# 1VFAT_OH1_OCT1.net
KiCad netlist of a schematic drawn in Altium Designer
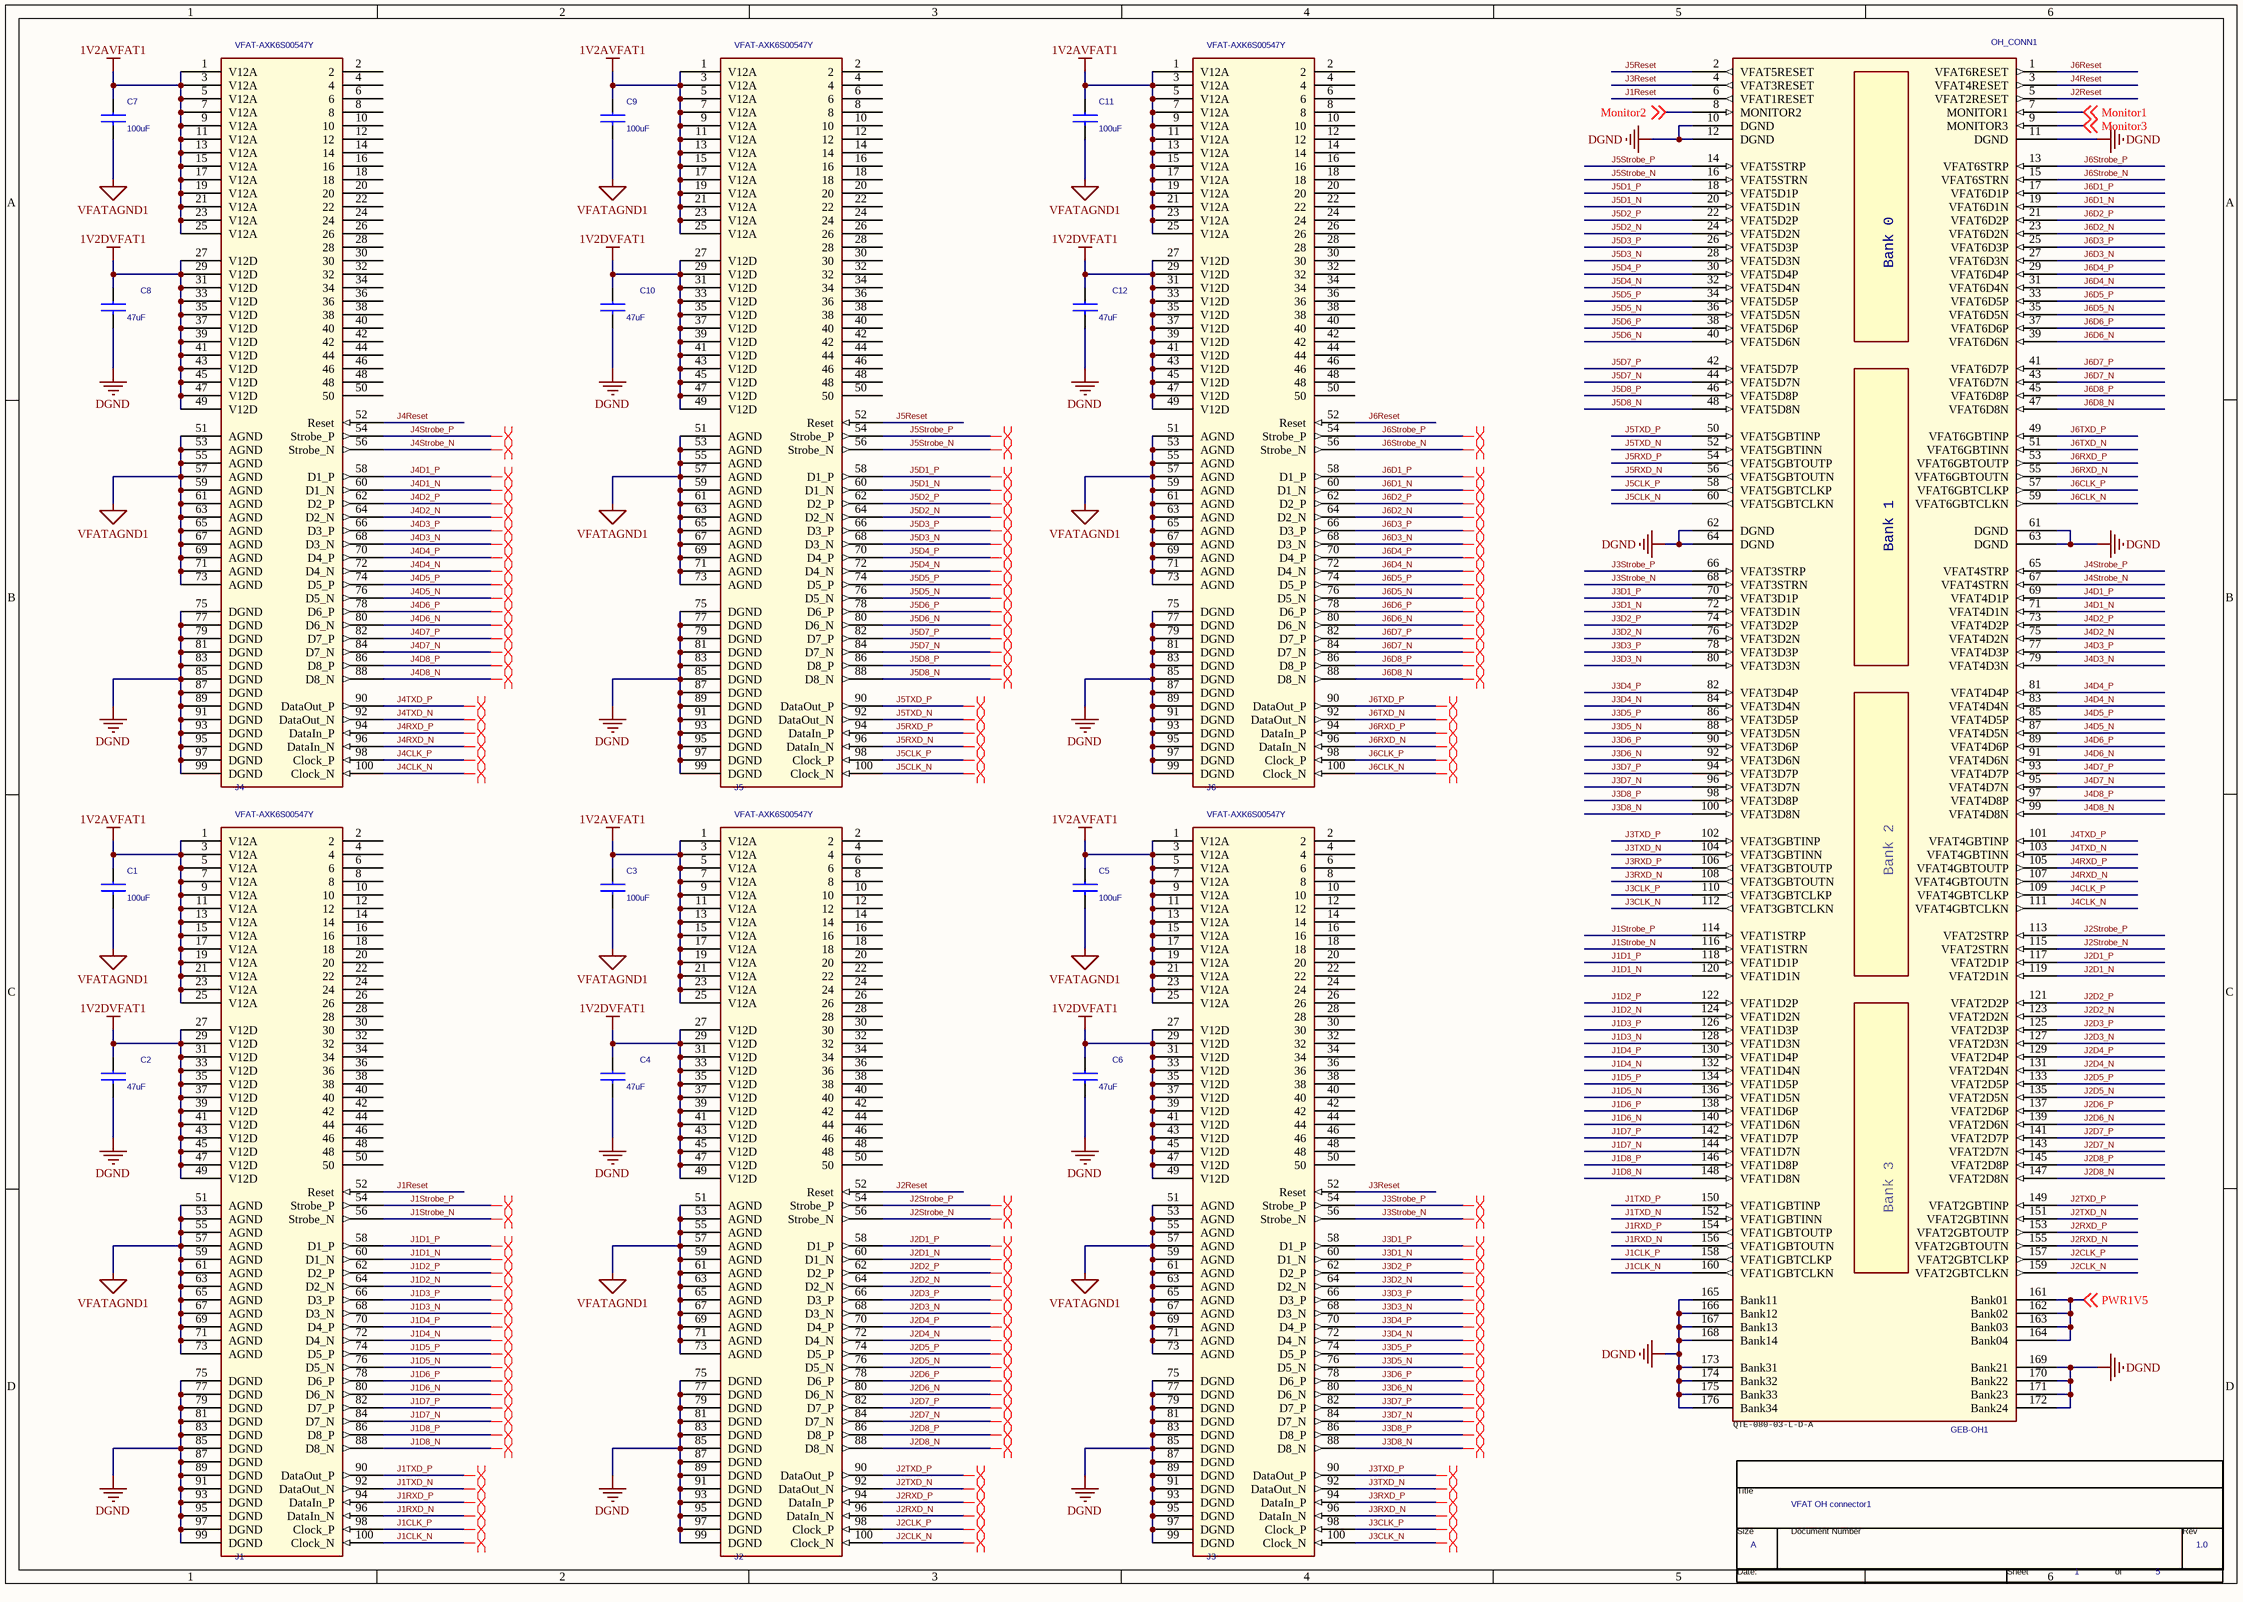
[diagram p0: 1VFAT_OH1_OCT1.SchDoc]

(export (version "E")
  (design (tool "Eeschema 10.0.6"))
  (components
    (comp (ref "*")
      (value "TitleBlock0")
      (fields
        (field (name "PAGE COUNT") "5")
        (field (name "PAGE NUMBER") "1")
        (field (name "PAGE SIZE") "A")
        (field (name "TITLE") "VFAT OH connector1")
        (field (name "REVCODE") "1.0")
      )
      (libsource (lib "*") (part "TitleBlock0"))
    )
    (comp (ref "C1") (value "100uF") (footprint "C1210") (libsource (lib "*") (part "CAP NP")))
    (comp (ref "C2") (value "47uF") (footprint "C1206") (libsource (lib "*") (part "CAP NP")))
    (comp (ref "C3") (value "100uF") (footprint "C1210") (libsource (lib "*") (part "CAP NP")))
    (comp (ref "C4") (value "47uF") (footprint "C1206") (libsource (lib "*") (part "CAP NP")))
    (comp (ref "C5") (value "100uF") (footprint "C1210") (libsource (lib "*") (part "CAP NP")))
    (comp (ref "C6") (value "47uF") (footprint "C1206") (libsource (lib "*") (part "CAP NP")))
    (comp (ref "C7") (value "100uF") (footprint "C1210") (libsource (lib "*") (part "CAP NP")))
    (comp (ref "C8") (value "47uF") (footprint "C1206") (libsource (lib "*") (part "CAP NP")))
    (comp (ref "C9") (value "100uF") (footprint "C1210") (libsource (lib "*") (part "CAP NP")))
    (comp (ref "C10") (value "47uF") (footprint "C1206") (libsource (lib "*") (part "CAP NP")))
    (comp (ref "C11") (value "100uF") (footprint "C1210") (libsource (lib "*") (part "CAP NP")))
    (comp (ref "C12") (value "47uF") (footprint "C1206") (libsource (lib "*") (part "CAP NP")))
    (comp (ref "J1")
      (value "VFAT-AXK6S00547Y")
      (footprint "panasonic100")
      (libsource (lib "*") (part "VFAT-AXK6S00547Y"))
    )
    (comp (ref "J2")
      (value "VFAT-AXK6S00547Y")
      (footprint "panasonic100")
      (libsource (lib "*") (part "VFAT-AXK6S00547Y"))
    )
    (comp (ref "J3")
      (value "VFAT-AXK6S00547Y")
      (footprint "panasonic100")
      (libsource (lib "*") (part "VFAT-AXK6S00547Y"))
    )
    (comp (ref "J4")
      (value "VFAT-AXK6S00547Y")
      (footprint "panasonic100")
      (libsource (lib "*") (part "VFAT-AXK6S00547Y"))
    )
    (comp (ref "J5")
      (value "VFAT-AXK6S00547Y")
      (footprint "panasonic100")
      (libsource (lib "*") (part "VFAT-AXK6S00547Y"))
    )
    (comp (ref "J6")
      (value "VFAT-AXK6S00547Y")
      (footprint "panasonic100")
      (libsource (lib "*") (part "VFAT-AXK6S00547Y"))
    )
    (comp (ref "OH_CONN1") (value "GEB-OH1") (footprint "samtec160") (libsource (lib "*") (part "GEB-OH1")))
  )
  (nets
    (net (code "1") (name "/J1CLK_N") (class "Default")
      (node (ref "J1") (pin "100") (pinfunction "Clock_N_100") (pintype "input"))
      (node (ref "OH_CONN1") (pin "160") (pinfunction "VFAT1GBTCLKN_160") (pintype "output"))
    )
    (net (code "2") (name "/J1CLK_P") (class "Default")
      (node (ref "J1") (pin "98") (pinfunction "Clock_P_98") (pintype "input"))
      (node (ref "OH_CONN1") (pin "158") (pinfunction "VFAT1GBTCLKP_158") (pintype "output"))
    )
    (net (code "3") (name "/J1D1_N") (class "Default")
      (node (ref "J1") (pin "60") (pinfunction "D1_N_60") (pintype "output"))
      (node (ref "OH_CONN1") (pin "120") (pinfunction "VFAT1D1N_120") (pintype "input"))
    )
    (net (code "4") (name "/J1D1_P") (class "Default")
      (node (ref "J1") (pin "58") (pinfunction "D1_P_58") (pintype "output"))
      (node (ref "OH_CONN1") (pin "118") (pinfunction "VFAT1D1P_118") (pintype "input"))
    )
    (net (code "5") (name "/J1D2_N") (class "Default")
      (node (ref "J1") (pin "64") (pinfunction "D2_N_64") (pintype "output"))
      (node (ref "OH_CONN1") (pin "124") (pinfunction "VFAT1D2N_124") (pintype "input"))
    )
    (net (code "6") (name "/J1D2_P") (class "Default")
      (node (ref "J1") (pin "62") (pinfunction "D2_P_62") (pintype "output"))
      (node (ref "OH_CONN1") (pin "122") (pinfunction "VFAT1D2P_122") (pintype "input"))
    )
    (net (code "7") (name "/J1D3_N") (class "Default")
      (node (ref "J1") (pin "68") (pinfunction "D3_N_68") (pintype "output"))
      (node (ref "OH_CONN1") (pin "128") (pinfunction "VFAT1D3N_128") (pintype "input"))
    )
    (net (code "8") (name "/J1D3_P") (class "Default")
      (node (ref "J1") (pin "66") (pinfunction "D3_P_66") (pintype "output"))
      (node (ref "OH_CONN1") (pin "126") (pinfunction "VFAT1D3P_126") (pintype "input"))
    )
    (net (code "9") (name "/J1D4_N") (class "Default")
      (node (ref "J1") (pin "72") (pinfunction "D4_N_72") (pintype "output"))
      (node (ref "OH_CONN1") (pin "132") (pinfunction "VFAT1D4N_132") (pintype "input"))
    )
    (net (code "10") (name "/J1D4_P") (class "Default")
      (node (ref "J1") (pin "70") (pinfunction "D4_P_70") (pintype "output"))
      (node (ref "OH_CONN1") (pin "130") (pinfunction "VFAT1D4P_130") (pintype "input"))
    )
    (net (code "11") (name "/J1D5_N") (class "Default")
      (node (ref "J1") (pin "76") (pinfunction "D5_N_76") (pintype "output"))
      (node (ref "OH_CONN1") (pin "136") (pinfunction "VFAT1D5N_136") (pintype "input"))
    )
    (net (code "12") (name "/J1D5_P") (class "Default")
      (node (ref "J1") (pin "74") (pinfunction "D5_P_74") (pintype "output"))
      (node (ref "OH_CONN1") (pin "134") (pinfunction "VFAT1D5P_134") (pintype "input"))
    )
    (net (code "13") (name "/J1D6_N") (class "Default")
      (node (ref "J1") (pin "80") (pinfunction "D6_N_80") (pintype "output"))
      (node (ref "OH_CONN1") (pin "140") (pinfunction "VFAT1D6N_140") (pintype "input"))
    )
    (net (code "14") (name "/J1D6_P") (class "Default")
      (node (ref "J1") (pin "78") (pinfunction "D6_P_78") (pintype "output"))
      (node (ref "OH_CONN1") (pin "138") (pinfunction "VFAT1D6P_138") (pintype "input"))
    )
    (net (code "15") (name "/J1D7_N") (class "Default")
      (node (ref "J1") (pin "84") (pinfunction "D7_N_84") (pintype "output"))
      (node (ref "OH_CONN1") (pin "144") (pinfunction "VFAT1D7N_144") (pintype "input"))
    )
    (net (code "16") (name "/J1D7_P") (class "Default")
      (node (ref "J1") (pin "82") (pinfunction "D7_P_82") (pintype "output"))
      (node (ref "OH_CONN1") (pin "142") (pinfunction "VFAT1D7P_142") (pintype "input"))
    )
    (net (code "17") (name "/J1D8_N") (class "Default")
      (node (ref "J1") (pin "88") (pinfunction "D8_N_88") (pintype "output"))
      (node (ref "OH_CONN1") (pin "148") (pinfunction "VFAT1D8N_148") (pintype "input"))
    )
    (net (code "18") (name "/J1D8_P") (class "Default")
      (node (ref "J1") (pin "86") (pinfunction "D8_P_86") (pintype "output"))
      (node (ref "OH_CONN1") (pin "146") (pinfunction "VFAT1D8P_146") (pintype "input"))
    )
    (net (code "19") (name "/J1RXD_N") (class "Default")
      (node (ref "J1") (pin "96") (pinfunction "DataIn_N_96") (pintype "input"))
      (node (ref "OH_CONN1") (pin "156") (pinfunction "VFAT1GBTOUTN_156") (pintype "output"))
    )
    (net (code "20") (name "/J1RXD_P") (class "Default")
      (node (ref "J1") (pin "94") (pinfunction "DataIn_P_94") (pintype "input"))
      (node (ref "OH_CONN1") (pin "154") (pinfunction "VFAT1GBTOUTP_154") (pintype "output"))
    )
    (net (code "21") (name "/J1Reset") (class "Default")
      (node (ref "J1") (pin "52") (pinfunction "Reset_52") (pintype "input"))
      (node (ref "OH_CONN1") (pin "6") (pinfunction "VFAT1RESET_6") (pintype "output"))
    )
    (net (code "22") (name "/J1Strobe_N") (class "Default")
      (node (ref "J1") (pin "56") (pinfunction "Strobe_N_56") (pintype "output"))
      (node (ref "OH_CONN1") (pin "116") (pinfunction "VFAT1STRN_116") (pintype "input"))
    )
    (net (code "23") (name "/J1Strobe_P") (class "Default")
      (node (ref "J1") (pin "54") (pinfunction "Strobe_P_54") (pintype "output"))
      (node (ref "OH_CONN1") (pin "114") (pinfunction "VFAT1STRP_114") (pintype "input"))
    )
    (net (code "24") (name "/J1TXD_N") (class "Default")
      (node (ref "J1") (pin "92") (pinfunction "DataOut_N_92") (pintype "output"))
      (node (ref "OH_CONN1") (pin "152") (pinfunction "VFAT1GBTINN_152") (pintype "input"))
    )
    (net (code "25") (name "/J1TXD_P") (class "Default")
      (node (ref "J1") (pin "90") (pinfunction "DataOut_P_90") (pintype "output"))
      (node (ref "OH_CONN1") (pin "150") (pinfunction "VFAT1GBTINP_150") (pintype "input"))
    )
    (net (code "26") (name "/J2CLK_N") (class "Default")
      (node (ref "J2") (pin "100") (pinfunction "Clock_N_100") (pintype "input"))
      (node (ref "OH_CONN1") (pin "159") (pinfunction "VFAT2GBTCLKN_159") (pintype "output"))
    )
    (net (code "27") (name "/J2CLK_P") (class "Default")
      (node (ref "J2") (pin "98") (pinfunction "Clock_P_98") (pintype "input"))
      (node (ref "OH_CONN1") (pin "157") (pinfunction "VFAT2GBTCLKP_157") (pintype "output"))
    )
    (net (code "28") (name "/J2D1_N") (class "Default")
      (node (ref "J2") (pin "60") (pinfunction "D1_N_60") (pintype "output"))
      (node (ref "OH_CONN1") (pin "119") (pinfunction "VFAT2D1N_119") (pintype "input"))
    )
    (net (code "29") (name "/J2D1_P") (class "Default")
      (node (ref "J2") (pin "58") (pinfunction "D1_P_58") (pintype "output"))
      (node (ref "OH_CONN1") (pin "117") (pinfunction "VFAT2D1P_117") (pintype "input"))
    )
    (net (code "30") (name "/J2D2_N") (class "Default")
      (node (ref "J2") (pin "64") (pinfunction "D2_N_64") (pintype "output"))
      (node (ref "OH_CONN1") (pin "123") (pinfunction "VFAT2D2N_123") (pintype "input"))
    )
    (net (code "31") (name "/J2D2_P") (class "Default")
      (node (ref "J2") (pin "62") (pinfunction "D2_P_62") (pintype "output"))
      (node (ref "OH_CONN1") (pin "121") (pinfunction "VFAT2D2P_121") (pintype "input"))
    )
    (net (code "32") (name "/J2D3_N") (class "Default")
      (node (ref "J2") (pin "68") (pinfunction "D3_N_68") (pintype "output"))
      (node (ref "OH_CONN1") (pin "127") (pinfunction "VFAT2D3N_127") (pintype "input"))
    )
    (net (code "33") (name "/J2D3_P") (class "Default")
      (node (ref "J2") (pin "66") (pinfunction "D3_P_66") (pintype "output"))
      (node (ref "OH_CONN1") (pin "125") (pinfunction "VFAT2D3P_125") (pintype "input"))
    )
    (net (code "34") (name "/J2D4_N") (class "Default")
      (node (ref "J2") (pin "72") (pinfunction "D4_N_72") (pintype "output"))
      (node (ref "OH_CONN1") (pin "131") (pinfunction "VFAT2D4N_131") (pintype "input"))
    )
    (net (code "35") (name "/J2D4_P") (class "Default")
      (node (ref "J2") (pin "70") (pinfunction "D4_P_70") (pintype "output"))
      (node (ref "OH_CONN1") (pin "129") (pinfunction "VFAT2D4P_129") (pintype "input"))
    )
    (net (code "36") (name "/J2D5_N") (class "Default")
      (node (ref "J2") (pin "76") (pinfunction "D5_N_76") (pintype "output"))
      (node (ref "OH_CONN1") (pin "135") (pinfunction "VFAT2D5N_135") (pintype "input"))
    )
    (net (code "37") (name "/J2D5_P") (class "Default")
      (node (ref "J2") (pin "74") (pinfunction "D5_P_74") (pintype "output"))
      (node (ref "OH_CONN1") (pin "133") (pinfunction "VFAT2D5P_133") (pintype "input"))
    )
    (net (code "38") (name "/J2D6_N") (class "Default")
      (node (ref "J2") (pin "80") (pinfunction "D6_N_80") (pintype "output"))
      (node (ref "OH_CONN1") (pin "139") (pinfunction "VFAT2D6N_139") (pintype "input"))
    )
    (net (code "39") (name "/J2D6_P") (class "Default")
      (node (ref "J2") (pin "78") (pinfunction "D6_P_78") (pintype "output"))
      (node (ref "OH_CONN1") (pin "137") (pinfunction "VFAT2D6P_137") (pintype "input"))
    )
    (net (code "40") (name "/J2D7_N") (class "Default")
      (node (ref "J2") (pin "84") (pinfunction "D7_N_84") (pintype "output"))
      (node (ref "OH_CONN1") (pin "143") (pinfunction "VFAT2D7N_143") (pintype "input"))
    )
    (net (code "41") (name "/J2D7_P") (class "Default")
      (node (ref "J2") (pin "82") (pinfunction "D7_P_82") (pintype "output"))
      (node (ref "OH_CONN1") (pin "141") (pinfunction "VFAT2D7P_141") (pintype "input"))
    )
    (net (code "42") (name "/J2D8_N") (class "Default")
      (node (ref "J2") (pin "88") (pinfunction "D8_N_88") (pintype "output"))
      (node (ref "OH_CONN1") (pin "147") (pinfunction "VFAT2D8N_147") (pintype "input"))
    )
    (net (code "43") (name "/J2D8_P") (class "Default")
      (node (ref "J2") (pin "86") (pinfunction "D8_P_86") (pintype "output"))
      (node (ref "OH_CONN1") (pin "145") (pinfunction "VFAT2D8P_145") (pintype "input"))
    )
    (net (code "44") (name "/J2RXD_N") (class "Default")
      (node (ref "J2") (pin "96") (pinfunction "DataIn_N_96") (pintype "input"))
      (node (ref "OH_CONN1") (pin "155") (pinfunction "VFAT2GBTOUTN_155") (pintype "output"))
    )
    (net (code "45") (name "/J2RXD_P") (class "Default")
      (node (ref "J2") (pin "94") (pinfunction "DataIn_P_94") (pintype "input"))
      (node (ref "OH_CONN1") (pin "153") (pinfunction "VFAT2GBTOUTP_153") (pintype "output"))
    )
    (net (code "46") (name "/J2Reset") (class "Default")
      (node (ref "J2") (pin "52") (pinfunction "Reset_52") (pintype "input"))
      (node (ref "OH_CONN1") (pin "5") (pinfunction "VFAT2RESET_5") (pintype "output"))
    )
    (net (code "47") (name "/J2Strobe_N") (class "Default")
      (node (ref "J2") (pin "56") (pinfunction "Strobe_N_56") (pintype "output"))
      (node (ref "OH_CONN1") (pin "115") (pinfunction "VFAT2STRN_115") (pintype "input"))
    )
    (net (code "48") (name "/J2Strobe_P") (class "Default")
      (node (ref "J2") (pin "54") (pinfunction "Strobe_P_54") (pintype "output"))
      (node (ref "OH_CONN1") (pin "113") (pinfunction "VFAT2STRP_113") (pintype "input"))
    )
    (net (code "49") (name "/J2TXD_N") (class "Default")
      (node (ref "J2") (pin "92") (pinfunction "DataOut_N_92") (pintype "output"))
      (node (ref "OH_CONN1") (pin "151") (pinfunction "VFAT2GBTINN_151") (pintype "input"))
    )
    (net (code "50") (name "/J2TXD_P") (class "Default")
      (node (ref "J2") (pin "90") (pinfunction "DataOut_P_90") (pintype "output"))
      (node (ref "OH_CONN1") (pin "149") (pinfunction "VFAT2GBTINP_149") (pintype "input"))
    )
    (net (code "51") (name "/J3CLK_N") (class "Default")
      (node (ref "J3") (pin "100") (pinfunction "Clock_N_100") (pintype "input"))
      (node (ref "OH_CONN1") (pin "112") (pinfunction "VFAT3GBTCLKN_112") (pintype "output"))
    )
    (net (code "52") (name "/J3CLK_P") (class "Default")
      (node (ref "J3") (pin "98") (pinfunction "Clock_P_98") (pintype "input"))
      (node (ref "OH_CONN1") (pin "110") (pinfunction "VFAT3GBTCLKP_110") (pintype "output"))
    )
    (net (code "53") (name "/J3D1_N") (class "Default")
      (node (ref "J3") (pin "60") (pinfunction "D1_N_60") (pintype "output"))
      (node (ref "OH_CONN1") (pin "72") (pinfunction "VFAT3D1N_72") (pintype "input"))
    )
    (net (code "54") (name "/J3D1_P") (class "Default")
      (node (ref "J3") (pin "58") (pinfunction "D1_P_58") (pintype "output"))
      (node (ref "OH_CONN1") (pin "70") (pinfunction "VFAT3D1P_70") (pintype "input"))
    )
    (net (code "55") (name "/J3D2_N") (class "Default")
      (node (ref "J3") (pin "64") (pinfunction "D2_N_64") (pintype "output"))
      (node (ref "OH_CONN1") (pin "76") (pinfunction "VFAT3D2N_76") (pintype "input"))
    )
    (net (code "56") (name "/J3D2_P") (class "Default")
      (node (ref "J3") (pin "62") (pinfunction "D2_P_62") (pintype "output"))
      (node (ref "OH_CONN1") (pin "74") (pinfunction "VFAT3D2P_74") (pintype "input"))
    )
    (net (code "57") (name "/J3D3_N") (class "Default")
      (node (ref "J3") (pin "68") (pinfunction "D3_N_68") (pintype "output"))
      (node (ref "OH_CONN1") (pin "80") (pinfunction "VFAT3D3N_80") (pintype "input"))
    )
    (net (code "58") (name "/J3D3_P") (class "Default")
      (node (ref "J3") (pin "66") (pinfunction "D3_P_66") (pintype "output"))
      (node (ref "OH_CONN1") (pin "78") (pinfunction "VFAT3D3P_78") (pintype "input"))
    )
    (net (code "59") (name "/J3D4_N") (class "Default")
      (node (ref "J3") (pin "72") (pinfunction "D4_N_72") (pintype "output"))
      (node (ref "OH_CONN1") (pin "84") (pinfunction "VFAT3D4N_84") (pintype "input"))
    )
    (net (code "60") (name "/J3D4_P") (class "Default")
      (node (ref "J3") (pin "70") (pinfunction "D4_P_70") (pintype "output"))
      (node (ref "OH_CONN1") (pin "82") (pinfunction "VFAT3D4P_82") (pintype "input"))
    )
    (net (code "61") (name "/J3D5_N") (class "Default")
      (node (ref "J3") (pin "76") (pinfunction "D5_N_76") (pintype "output"))
      (node (ref "OH_CONN1") (pin "88") (pinfunction "VFAT3D5N_88") (pintype "input"))
    )
    (net (code "62") (name "/J3D5_P") (class "Default")
      (node (ref "J3") (pin "74") (pinfunction "D5_P_74") (pintype "output"))
      (node (ref "OH_CONN1") (pin "86") (pinfunction "VFAT3D5P_86") (pintype "input"))
    )
    (net (code "63") (name "/J3D6_N") (class "Default")
      (node (ref "J3") (pin "80") (pinfunction "D6_N_80") (pintype "output"))
      (node (ref "OH_CONN1") (pin "92") (pinfunction "VFAT3D6N_92") (pintype "input"))
    )
    (net (code "64") (name "/J3D6_P") (class "Default")
      (node (ref "J3") (pin "78") (pinfunction "D6_P_78") (pintype "output"))
      (node (ref "OH_CONN1") (pin "90") (pinfunction "VFAT3D6P_90") (pintype "input"))
    )
    (net (code "65") (name "/J3D7_N") (class "Default")
      (node (ref "J3") (pin "84") (pinfunction "D7_N_84") (pintype "output"))
      (node (ref "OH_CONN1") (pin "96") (pinfunction "VFAT3D7N_96") (pintype "input"))
    )
    (net (code "66") (name "/J3D7_P") (class "Default")
      (node (ref "J3") (pin "82") (pinfunction "D7_P_82") (pintype "output"))
      (node (ref "OH_CONN1") (pin "94") (pinfunction "VFAT3D7P_94") (pintype "input"))
    )
    (net (code "67") (name "/J3D8_N") (class "Default")
      (node (ref "J3") (pin "88") (pinfunction "D8_N_88") (pintype "output"))
      (node (ref "OH_CONN1") (pin "100") (pinfunction "VFAT3D8N_100") (pintype "input"))
    )
    (net (code "68") (name "/J3D8_P") (class "Default")
      (node (ref "J3") (pin "86") (pinfunction "D8_P_86") (pintype "output"))
      (node (ref "OH_CONN1") (pin "98") (pinfunction "VFAT3D8P_98") (pintype "input"))
    )
    (net (code "69") (name "/J3RXD_N") (class "Default")
      (node (ref "J3") (pin "96") (pinfunction "DataIn_N_96") (pintype "input"))
      (node (ref "OH_CONN1") (pin "108") (pinfunction "VFAT3GBTOUTN_108") (pintype "output"))
    )
    (net (code "70") (name "/J3RXD_P") (class "Default")
      (node (ref "J3") (pin "94") (pinfunction "DataIn_P_94") (pintype "input"))
      (node (ref "OH_CONN1") (pin "106") (pinfunction "VFAT3GBTOUTP_106") (pintype "output"))
    )
    (net (code "71") (name "/J3Reset") (class "Default")
      (node (ref "J3") (pin "52") (pinfunction "Reset_52") (pintype "input"))
      (node (ref "OH_CONN1") (pin "4") (pinfunction "VFAT3RESET_4") (pintype "output"))
    )
    (net (code "72") (name "/J3Strobe_N") (class "Default")
      (node (ref "J3") (pin "56") (pinfunction "Strobe_N_56") (pintype "output"))
      (node (ref "OH_CONN1") (pin "68") (pinfunction "VFAT3STRN_68") (pintype "input"))
    )
    (net (code "73") (name "/J3Strobe_P") (class "Default")
      (node (ref "J3") (pin "54") (pinfunction "Strobe_P_54") (pintype "output"))
      (node (ref "OH_CONN1") (pin "66") (pinfunction "VFAT3STRP_66") (pintype "input"))
    )
    (net (code "74") (name "/J3TXD_N") (class "Default")
      (node (ref "J3") (pin "92") (pinfunction "DataOut_N_92") (pintype "output"))
      (node (ref "OH_CONN1") (pin "104") (pinfunction "VFAT3GBTINN_104") (pintype "input"))
    )
    (net (code "75") (name "/J3TXD_P") (class "Default")
      (node (ref "J3") (pin "90") (pinfunction "DataOut_P_90") (pintype "output"))
      (node (ref "OH_CONN1") (pin "102") (pinfunction "VFAT3GBTINP_102") (pintype "input"))
    )
    (net (code "76") (name "/J4CLK_N") (class "Default")
      (node (ref "J4") (pin "100") (pinfunction "Clock_N_100") (pintype "input"))
      (node (ref "OH_CONN1") (pin "111") (pinfunction "VFAT4GBTCLKN_111") (pintype "output"))
    )
    (net (code "77") (name "/J4CLK_P") (class "Default")
      (node (ref "J4") (pin "98") (pinfunction "Clock_P_98") (pintype "input"))
      (node (ref "OH_CONN1") (pin "109") (pinfunction "VFAT4GBTCLKP_109") (pintype "output"))
    )
    (net (code "78") (name "/J4D1_N") (class "Default")
      (node (ref "J4") (pin "60") (pinfunction "D1_N_60") (pintype "output"))
      (node (ref "OH_CONN1") (pin "71") (pinfunction "VFAT4D1N_71") (pintype "input"))
    )
    (net (code "79") (name "/J4D1_P") (class "Default")
      (node (ref "J4") (pin "58") (pinfunction "D1_P_58") (pintype "output"))
      (node (ref "OH_CONN1") (pin "69") (pinfunction "VFAT4D1P_69") (pintype "input"))
    )
    (net (code "80") (name "/J4D2_N") (class "Default")
      (node (ref "J4") (pin "64") (pinfunction "D2_N_64") (pintype "output"))
      (node (ref "OH_CONN1") (pin "75") (pinfunction "VFAT4D2N_75") (pintype "input"))
    )
    (net (code "81") (name "/J4D2_P") (class "Default")
      (node (ref "J4") (pin "62") (pinfunction "D2_P_62") (pintype "output"))
      (node (ref "OH_CONN1") (pin "73") (pinfunction "VFAT4D2P_73") (pintype "input"))
    )
    (net (code "82") (name "/J4D3_N") (class "Default")
      (node (ref "J4") (pin "68") (pinfunction "D3_N_68") (pintype "output"))
      (node (ref "OH_CONN1") (pin "79") (pinfunction "VFAT4D3N_79") (pintype "input"))
    )
    (net (code "83") (name "/J4D3_P") (class "Default")
      (node (ref "J4") (pin "66") (pinfunction "D3_P_66") (pintype "output"))
      (node (ref "OH_CONN1") (pin "77") (pinfunction "VFAT4D3P_77") (pintype "input"))
    )
    (net (code "84") (name "/J4D4_N") (class "Default")
      (node (ref "J4") (pin "72") (pinfunction "D4_N_72") (pintype "output"))
      (node (ref "OH_CONN1") (pin "83") (pinfunction "VFAT4D4N_83") (pintype "input"))
    )
    (net (code "85") (name "/J4D4_P") (class "Default")
      (node (ref "J4") (pin "70") (pinfunction "D4_P_70") (pintype "output"))
      (node (ref "OH_CONN1") (pin "81") (pinfunction "VFAT4D4P_81") (pintype "input"))
    )
    (net (code "86") (name "/J4D5_N") (class "Default")
      (node (ref "J4") (pin "76") (pinfunction "D5_N_76") (pintype "output"))
      (node (ref "OH_CONN1") (pin "87") (pinfunction "VFAT4D5N_87") (pintype "input"))
    )
    (net (code "87") (name "/J4D5_P") (class "Default")
      (node (ref "J4") (pin "74") (pinfunction "D5_P_74") (pintype "output"))
      (node (ref "OH_CONN1") (pin "85") (pinfunction "VFAT4D5P_85") (pintype "input"))
    )
    (net (code "88") (name "/J4D6_N") (class "Default")
      (node (ref "J4") (pin "80") (pinfunction "D6_N_80") (pintype "output"))
      (node (ref "OH_CONN1") (pin "91") (pinfunction "VFAT4D6N_91") (pintype "input"))
    )
    (net (code "89") (name "/J4D6_P") (class "Default")
      (node (ref "J4") (pin "78") (pinfunction "D6_P_78") (pintype "output"))
      (node (ref "OH_CONN1") (pin "89") (pinfunction "VFAT4D6P_89") (pintype "input"))
    )
    (net (code "90") (name "/J4D7_N") (class "Default")
      (node (ref "J4") (pin "84") (pinfunction "D7_N_84") (pintype "output"))
      (node (ref "OH_CONN1") (pin "95") (pinfunction "VFAT4D7N_95") (pintype "input"))
    )
    (net (code "91") (name "/J4D7_P") (class "Default")
      (node (ref "J4") (pin "82") (pinfunction "D7_P_82") (pintype "output"))
      (node (ref "OH_CONN1") (pin "93") (pinfunction "VFAT4D7P_93") (pintype "input"))
    )
    (net (code "92") (name "/J4D8_N") (class "Default")
      (node (ref "J4") (pin "88") (pinfunction "D8_N_88") (pintype "output"))
      (node (ref "OH_CONN1") (pin "99") (pinfunction "VFAT4D8N_99") (pintype "input"))
    )
    (net (code "93") (name "/J4D8_P") (class "Default")
      (node (ref "J4") (pin "86") (pinfunction "D8_P_86") (pintype "output"))
      (node (ref "OH_CONN1") (pin "97") (pinfunction "VFAT4D8P_97") (pintype "input"))
    )
    (net (code "94") (name "/J4RXD_N") (class "Default")
      (node (ref "J4") (pin "96") (pinfunction "DataIn_N_96") (pintype "input"))
      (node (ref "OH_CONN1") (pin "107") (pinfunction "VFAT4GBTOUTN_107") (pintype "output"))
    )
    (net (code "95") (name "/J4RXD_P") (class "Default")
      (node (ref "J4") (pin "94") (pinfunction "DataIn_P_94") (pintype "input"))
      (node (ref "OH_CONN1") (pin "105") (pinfunction "VFAT4GBTOUTP_105") (pintype "output"))
    )
    (net (code "96") (name "/J4Reset") (class "Default")
      (node (ref "J4") (pin "52") (pinfunction "Reset_52") (pintype "input"))
      (node (ref "OH_CONN1") (pin "3") (pinfunction "VFAT4RESET_3") (pintype "output"))
    )
    (net (code "97") (name "/J4Strobe_N") (class "Default")
      (node (ref "J4") (pin "56") (pinfunction "Strobe_N_56") (pintype "output"))
      (node (ref "OH_CONN1") (pin "67") (pinfunction "VFAT4STRN_67") (pintype "input"))
    )
    (net (code "98") (name "/J4Strobe_P") (class "Default")
      (node (ref "J4") (pin "54") (pinfunction "Strobe_P_54") (pintype "output"))
      (node (ref "OH_CONN1") (pin "65") (pinfunction "VFAT4STRP_65") (pintype "input"))
    )
    (net (code "99") (name "/J4TXD_N") (class "Default")
      (node (ref "J4") (pin "92") (pinfunction "DataOut_N_92") (pintype "output"))
      (node (ref "OH_CONN1") (pin "103") (pinfunction "VFAT4GBTINN_103") (pintype "input"))
    )
    (net (code "100") (name "/J4TXD_P") (class "Default")
      (node (ref "J4") (pin "90") (pinfunction "DataOut_P_90") (pintype "output"))
      (node (ref "OH_CONN1") (pin "101") (pinfunction "VFAT4GBTINP_101") (pintype "input"))
    )
    (net (code "101") (name "/J5CLK_N") (class "Default")
      (node (ref "J5") (pin "100") (pinfunction "Clock_N_100") (pintype "input"))
      (node (ref "OH_CONN1") (pin "60") (pinfunction "VFAT5GBTCLKN_60") (pintype "output"))
    )
    (net (code "102") (name "/J5CLK_P") (class "Default")
      (node (ref "J5") (pin "98") (pinfunction "Clock_P_98") (pintype "input"))
      (node (ref "OH_CONN1") (pin "58") (pinfunction "VFAT5GBTCLKP_58") (pintype "output"))
    )
    (net (code "103") (name "/J5D1_N") (class "Default")
      (node (ref "J5") (pin "60") (pinfunction "D1_N_60") (pintype "output"))
      (node (ref "OH_CONN1") (pin "20") (pinfunction "VFAT5D1N_20") (pintype "input"))
    )
    (net (code "104") (name "/J5D1_P") (class "Default")
      (node (ref "J5") (pin "58") (pinfunction "D1_P_58") (pintype "output"))
      (node (ref "OH_CONN1") (pin "18") (pinfunction "VFAT5D1P_18") (pintype "input"))
    )
    (net (code "105") (name "/J5D2_N") (class "Default")
      (node (ref "J5") (pin "64") (pinfunction "D2_N_64") (pintype "output"))
      (node (ref "OH_CONN1") (pin "24") (pinfunction "VFAT5D2N_24") (pintype "input"))
    )
    (net (code "106") (name "/J5D2_P") (class "Default")
      (node (ref "J5") (pin "62") (pinfunction "D2_P_62") (pintype "output"))
      (node (ref "OH_CONN1") (pin "22") (pinfunction "VFAT5D2P_22") (pintype "input"))
    )
    (net (code "107") (name "/J5D3_N") (class "Default")
      (node (ref "J5") (pin "68") (pinfunction "D3_N_68") (pintype "output"))
      (node (ref "OH_CONN1") (pin "28") (pinfunction "VFAT5D3N_28") (pintype "input"))
    )
    (net (code "108") (name "/J5D3_P") (class "Default")
      (node (ref "J5") (pin "66") (pinfunction "D3_P_66") (pintype "output"))
      (node (ref "OH_CONN1") (pin "26") (pinfunction "VFAT5D3P_26") (pintype "input"))
    )
    (net (code "109") (name "/J5D4_N") (class "Default")
      (node (ref "J5") (pin "72") (pinfunction "D4_N_72") (pintype "output"))
      (node (ref "OH_CONN1") (pin "32") (pinfunction "VFAT5D4N_32") (pintype "input"))
    )
    (net (code "110") (name "/J5D4_P") (class "Default")
      (node (ref "J5") (pin "70") (pinfunction "D4_P_70") (pintype "output"))
      (node (ref "OH_CONN1") (pin "30") (pinfunction "VFAT5D4P_30") (pintype "input"))
    )
    (net (code "111") (name "/J5D5_N") (class "Default")
      (node (ref "J5") (pin "76") (pinfunction "D5_N_76") (pintype "output"))
      (node (ref "OH_CONN1") (pin "36") (pinfunction "VFAT5D5N_36") (pintype "input"))
    )
    (net (code "112") (name "/J5D5_P") (class "Default")
      (node (ref "J5") (pin "74") (pinfunction "D5_P_74") (pintype "output"))
      (node (ref "OH_CONN1") (pin "34") (pinfunction "VFAT5D5P_34") (pintype "input"))
    )
    (net (code "113") (name "/J5D6_N") (class "Default")
      (node (ref "J5") (pin "80") (pinfunction "D6_N_80") (pintype "output"))
      (node (ref "OH_CONN1") (pin "40") (pinfunction "VFAT5D6N_40") (pintype "input"))
    )
    (net (code "114") (name "/J5D6_P") (class "Default")
      (node (ref "J5") (pin "78") (pinfunction "D6_P_78") (pintype "output"))
      (node (ref "OH_CONN1") (pin "38") (pinfunction "VFAT5D6P_38") (pintype "input"))
    )
    (net (code "115") (name "/J5D7_N") (class "Default")
      (node (ref "J5") (pin "84") (pinfunction "D7_N_84") (pintype "output"))
      (node (ref "OH_CONN1") (pin "44") (pinfunction "VFAT5D7N_44") (pintype "input"))
    )
    (net (code "116") (name "/J5D7_P") (class "Default")
      (node (ref "J5") (pin "82") (pinfunction "D7_P_82") (pintype "output"))
      (node (ref "OH_CONN1") (pin "42") (pinfunction "VFAT5D7P_42") (pintype "input"))
    )
    (net (code "117") (name "/J5D8_N") (class "Default")
      (node (ref "J5") (pin "88") (pinfunction "D8_N_88") (pintype "output"))
      (node (ref "OH_CONN1") (pin "48") (pinfunction "VFAT5D8N_48") (pintype "input"))
    )
    (net (code "118") (name "/J5D8_P") (class "Default")
      (node (ref "J5") (pin "86") (pinfunction "D8_P_86") (pintype "output"))
      (node (ref "OH_CONN1") (pin "46") (pinfunction "VFAT5D8P_46") (pintype "input"))
    )
    (net (code "119") (name "/J5RXD_N") (class "Default")
      (node (ref "J5") (pin "96") (pinfunction "DataIn_N_96") (pintype "input"))
      (node (ref "OH_CONN1") (pin "56") (pinfunction "VFAT5GBTOUTN_56") (pintype "output"))
    )
    (net (code "120") (name "/J5RXD_P") (class "Default")
      (node (ref "J5") (pin "94") (pinfunction "DataIn_P_94") (pintype "input"))
      (node (ref "OH_CONN1") (pin "54") (pinfunction "VFAT5GBTOUTP_54") (pintype "output"))
    )
    (net (code "121") (name "/J5Reset") (class "Default")
      (node (ref "J5") (pin "52") (pinfunction "Reset_52") (pintype "input"))
      (node (ref "OH_CONN1") (pin "2") (pinfunction "VFAT5RESET_2") (pintype "output"))
    )
    (net (code "122") (name "/J5Strobe_N") (class "Default")
      (node (ref "J5") (pin "56") (pinfunction "Strobe_N_56") (pintype "output"))
      (node (ref "OH_CONN1") (pin "16") (pinfunction "VFAT5STRN_16") (pintype "input"))
    )
    (net (code "123") (name "/J5Strobe_P") (class "Default")
      (node (ref "J5") (pin "54") (pinfunction "Strobe_P_54") (pintype "output"))
      (node (ref "OH_CONN1") (pin "14") (pinfunction "VFAT5STRP_14") (pintype "input"))
    )
    (net (code "124") (name "/J5TXD_N") (class "Default")
      (node (ref "J5") (pin "92") (pinfunction "DataOut_N_92") (pintype "output"))
      (node (ref "OH_CONN1") (pin "52") (pinfunction "VFAT5GBTINN_52") (pintype "input"))
    )
    (net (code "125") (name "/J5TXD_P") (class "Default")
      (node (ref "J5") (pin "90") (pinfunction "DataOut_P_90") (pintype "output"))
      (node (ref "OH_CONN1") (pin "50") (pinfunction "VFAT5GBTINP_50") (pintype "input"))
    )
    (net (code "126") (name "/J6CLK_N") (class "Default")
      (node (ref "J6") (pin "100") (pinfunction "Clock_N_100") (pintype "input"))
      (node (ref "OH_CONN1") (pin "59") (pinfunction "VFAT6GBTCLKN_59") (pintype "output"))
    )
    (net (code "127") (name "/J6CLK_P") (class "Default")
      (node (ref "J6") (pin "98") (pinfunction "Clock_P_98") (pintype "input"))
      (node (ref "OH_CONN1") (pin "57") (pinfunction "VFAT6GBTCLKP_57") (pintype "output"))
    )
    (net (code "128") (name "/J6D1_N") (class "Default")
      (node (ref "J6") (pin "60") (pinfunction "D1_N_60") (pintype "output"))
      (node (ref "OH_CONN1") (pin "19") (pinfunction "VFAT6D1N_19") (pintype "input"))
    )
    (net (code "129") (name "/J6D1_P") (class "Default")
      (node (ref "J6") (pin "58") (pinfunction "D1_P_58") (pintype "output"))
      (node (ref "OH_CONN1") (pin "17") (pinfunction "VFAT6D1P_17") (pintype "input"))
    )
    (net (code "130") (name "/J6D2_N") (class "Default")
      (node (ref "J6") (pin "64") (pinfunction "D2_N_64") (pintype "output"))
      (node (ref "OH_CONN1") (pin "23") (pinfunction "VFAT6D2N_23") (pintype "input"))
    )
    (net (code "131") (name "/J6D2_P") (class "Default")
      (node (ref "J6") (pin "62") (pinfunction "D2_P_62") (pintype "output"))
      (node (ref "OH_CONN1") (pin "21") (pinfunction "VFAT6D2P_21") (pintype "input"))
    )
    (net (code "132") (name "/J6D3_N") (class "Default")
      (node (ref "J6") (pin "68") (pinfunction "D3_N_68") (pintype "output"))
      (node (ref "OH_CONN1") (pin "27") (pinfunction "VFAT6D3N_27") (pintype "input"))
    )
    (net (code "133") (name "/J6D3_P") (class "Default")
      (node (ref "J6") (pin "66") (pinfunction "D3_P_66") (pintype "output"))
      (node (ref "OH_CONN1") (pin "25") (pinfunction "VFAT6D3P_25") (pintype "input"))
    )
    (net (code "134") (name "/J6D4_N") (class "Default")
      (node (ref "J6") (pin "72") (pinfunction "D4_N_72") (pintype "output"))
      (node (ref "OH_CONN1") (pin "31") (pinfunction "VFAT6D4N_31") (pintype "input"))
    )
    (net (code "135") (name "/J6D4_P") (class "Default")
      (node (ref "J6") (pin "70") (pinfunction "D4_P_70") (pintype "output"))
      (node (ref "OH_CONN1") (pin "29") (pinfunction "VFAT6D4P_29") (pintype "input"))
    )
    (net (code "136") (name "/J6D5_N") (class "Default")
      (node (ref "J6") (pin "76") (pinfunction "D5_N_76") (pintype "output"))
      (node (ref "OH_CONN1") (pin "35") (pinfunction "VFAT6D5N_35") (pintype "input"))
    )
    (net (code "137") (name "/J6D5_P") (class "Default")
      (node (ref "J6") (pin "74") (pinfunction "D5_P_74") (pintype "output"))
      (node (ref "OH_CONN1") (pin "33") (pinfunction "VFAT6D5P_33") (pintype "input"))
    )
    (net (code "138") (name "/J6D6_N") (class "Default")
      (node (ref "J6") (pin "80") (pinfunction "D6_N_80") (pintype "output"))
      (node (ref "OH_CONN1") (pin "39") (pinfunction "VFAT6D6N_39") (pintype "input"))
    )
    (net (code "139") (name "/J6D6_P") (class "Default")
      (node (ref "J6") (pin "78") (pinfunction "D6_P_78") (pintype "output"))
      (node (ref "OH_CONN1") (pin "37") (pinfunction "VFAT6D6P_37") (pintype "input"))
    )
    (net (code "140") (name "/J6D7_N") (class "Default")
      (node (ref "J6") (pin "84") (pinfunction "D7_N_84") (pintype "output"))
      (node (ref "OH_CONN1") (pin "43") (pinfunction "VFAT6D7N_43") (pintype "input"))
    )
    (net (code "141") (name "/J6D7_P") (class "Default")
      (node (ref "J6") (pin "82") (pinfunction "D7_P_82") (pintype "output"))
      (node (ref "OH_CONN1") (pin "41") (pinfunction "VFAT6D7P_41") (pintype "input"))
    )
    (net (code "142") (name "/J6D8_N") (class "Default")
      (node (ref "J6") (pin "88") (pinfunction "D8_N_88") (pintype "output"))
      (node (ref "OH_CONN1") (pin "47") (pinfunction "VFAT6D8N_47") (pintype "input"))
    )
    (net (code "143") (name "/J6D8_P") (class "Default")
      (node (ref "J6") (pin "86") (pinfunction "D8_P_86") (pintype "output"))
      (node (ref "OH_CONN1") (pin "45") (pinfunction "VFAT6D8P_45") (pintype "input"))
    )
    (net (code "144") (name "/J6RXD_N") (class "Default")
      (node (ref "J6") (pin "96") (pinfunction "DataIn_N_96") (pintype "input"))
      (node (ref "OH_CONN1") (pin "55") (pinfunction "VFAT6GBTOUTN_55") (pintype "output"))
    )
    (net (code "145") (name "/J6RXD_P") (class "Default")
      (node (ref "J6") (pin "94") (pinfunction "DataIn_P_94") (pintype "input"))
      (node (ref "OH_CONN1") (pin "53") (pinfunction "VFAT6GBTOUTP_53") (pintype "output"))
    )
    (net (code "146") (name "/J6Reset") (class "Default")
      (node (ref "J6") (pin "52") (pinfunction "Reset_52") (pintype "input"))
      (node (ref "OH_CONN1") (pin "1") (pinfunction "VFAT6RESET_1") (pintype "output"))
    )
    (net (code "147") (name "/J6Strobe_N") (class "Default")
      (node (ref "J6") (pin "56") (pinfunction "Strobe_N_56") (pintype "output"))
      (node (ref "OH_CONN1") (pin "15") (pinfunction "VFAT6STRN_15") (pintype "input"))
    )
    (net (code "148") (name "/J6Strobe_P") (class "Default")
      (node (ref "J6") (pin "54") (pinfunction "Strobe_P_54") (pintype "output"))
      (node (ref "OH_CONN1") (pin "13") (pinfunction "VFAT6STRP_13") (pintype "input"))
    )
    (net (code "149") (name "/J6TXD_N") (class "Default")
      (node (ref "J6") (pin "92") (pinfunction "DataOut_N_92") (pintype "output"))
      (node (ref "OH_CONN1") (pin "51") (pinfunction "VFAT6GBTINN_51") (pintype "input"))
    )
    (net (code "150") (name "/J6TXD_P") (class "Default")
      (node (ref "J6") (pin "90") (pinfunction "DataOut_P_90") (pintype "output"))
      (node (ref "OH_CONN1") (pin "49") (pinfunction "VFAT6GBTINP_49") (pintype "input"))
    )
    (net (code "151") (name "1V2AVFAT1") (class "Default")
      (node (ref "C1") (pin "1") (pinfunction "1_1") (pintype "passive"))
      (node (ref "C11") (pin "1") (pinfunction "1_1") (pintype "passive"))
      (node (ref "C3") (pin "1") (pinfunction "1_1") (pintype "passive"))
      (node (ref "C5") (pin "1") (pinfunction "1_1") (pintype "passive"))
      (node (ref "C7") (pin "1") (pinfunction "1_1") (pintype "passive"))
      (node (ref "C9") (pin "1") (pinfunction "1_1") (pintype "passive"))
      (node (ref "J1") (pin "1") (pinfunction "V12A_1") (pintype "power_in"))
      (node (ref "J1") (pin "11") (pinfunction "V12A_11") (pintype "power_in"))
      (node (ref "J1") (pin "13") (pinfunction "V12A_13") (pintype "power_in"))
      (node (ref "J1") (pin "15") (pinfunction "V12A_15") (pintype "power_in"))
      (node (ref "J1") (pin "17") (pinfunction "V12A_17") (pintype "power_in"))
      (node (ref "J1") (pin "19") (pinfunction "V12A_19") (pintype "power_in"))
      (node (ref "J1") (pin "21") (pinfunction "V12A_21") (pintype "power_in"))
      (node (ref "J1") (pin "23") (pinfunction "V12A_23") (pintype "power_in"))
      (node (ref "J1") (pin "25") (pinfunction "V12A_25") (pintype "power_in"))
      (node (ref "J1") (pin "3") (pinfunction "V12A_3") (pintype "power_in"))
      (node (ref "J1") (pin "5") (pinfunction "V12A_5") (pintype "power_in"))
      (node (ref "J1") (pin "7") (pinfunction "V12A_7") (pintype "power_in"))
      (node (ref "J1") (pin "9") (pinfunction "V12A_9") (pintype "power_in"))
      (node (ref "J2") (pin "1") (pinfunction "V12A_1") (pintype "power_in"))
      (node (ref "J2") (pin "11") (pinfunction "V12A_11") (pintype "power_in"))
      (node (ref "J2") (pin "13") (pinfunction "V12A_13") (pintype "power_in"))
      (node (ref "J2") (pin "15") (pinfunction "V12A_15") (pintype "power_in"))
      (node (ref "J2") (pin "17") (pinfunction "V12A_17") (pintype "power_in"))
      (node (ref "J2") (pin "19") (pinfunction "V12A_19") (pintype "power_in"))
      (node (ref "J2") (pin "21") (pinfunction "V12A_21") (pintype "power_in"))
      (node (ref "J2") (pin "23") (pinfunction "V12A_23") (pintype "power_in"))
      (node (ref "J2") (pin "25") (pinfunction "V12A_25") (pintype "power_in"))
      (node (ref "J2") (pin "3") (pinfunction "V12A_3") (pintype "power_in"))
      (node (ref "J2") (pin "5") (pinfunction "V12A_5") (pintype "power_in"))
      (node (ref "J2") (pin "7") (pinfunction "V12A_7") (pintype "power_in"))
      (node (ref "J2") (pin "9") (pinfunction "V12A_9") (pintype "power_in"))
      (node (ref "J3") (pin "1") (pinfunction "V12A_1") (pintype "power_in"))
      (node (ref "J3") (pin "11") (pinfunction "V12A_11") (pintype "power_in"))
      (node (ref "J3") (pin "13") (pinfunction "V12A_13") (pintype "power_in"))
      (node (ref "J3") (pin "15") (pinfunction "V12A_15") (pintype "power_in"))
      (node (ref "J3") (pin "17") (pinfunction "V12A_17") (pintype "power_in"))
      (node (ref "J3") (pin "19") (pinfunction "V12A_19") (pintype "power_in"))
      (node (ref "J3") (pin "21") (pinfunction "V12A_21") (pintype "power_in"))
      (node (ref "J3") (pin "23") (pinfunction "V12A_23") (pintype "power_in"))
      (node (ref "J3") (pin "25") (pinfunction "V12A_25") (pintype "power_in"))
      (node (ref "J3") (pin "3") (pinfunction "V12A_3") (pintype "power_in"))
      (node (ref "J3") (pin "5") (pinfunction "V12A_5") (pintype "power_in"))
      (node (ref "J3") (pin "7") (pinfunction "V12A_7") (pintype "power_in"))
      (node (ref "J3") (pin "9") (pinfunction "V12A_9") (pintype "power_in"))
      (node (ref "J4") (pin "1") (pinfunction "V12A_1") (pintype "power_in"))
      (node (ref "J4") (pin "11") (pinfunction "V12A_11") (pintype "power_in"))
      (node (ref "J4") (pin "13") (pinfunction "V12A_13") (pintype "power_in"))
      (node (ref "J4") (pin "15") (pinfunction "V12A_15") (pintype "power_in"))
      (node (ref "J4") (pin "17") (pinfunction "V12A_17") (pintype "power_in"))
      (node (ref "J4") (pin "19") (pinfunction "V12A_19") (pintype "power_in"))
      (node (ref "J4") (pin "21") (pinfunction "V12A_21") (pintype "power_in"))
      (node (ref "J4") (pin "23") (pinfunction "V12A_23") (pintype "power_in"))
      (node (ref "J4") (pin "25") (pinfunction "V12A_25") (pintype "power_in"))
      (node (ref "J4") (pin "3") (pinfunction "V12A_3") (pintype "power_in"))
      (node (ref "J4") (pin "5") (pinfunction "V12A_5") (pintype "power_in"))
      (node (ref "J4") (pin "7") (pinfunction "V12A_7") (pintype "power_in"))
      (node (ref "J4") (pin "9") (pinfunction "V12A_9") (pintype "power_in"))
      (node (ref "J5") (pin "1") (pinfunction "V12A_1") (pintype "power_in"))
      (node (ref "J5") (pin "11") (pinfunction "V12A_11") (pintype "power_in"))
      (node (ref "J5") (pin "13") (pinfunction "V12A_13") (pintype "power_in"))
      (node (ref "J5") (pin "15") (pinfunction "V12A_15") (pintype "power_in"))
      (node (ref "J5") (pin "17") (pinfunction "V12A_17") (pintype "power_in"))
      (node (ref "J5") (pin "19") (pinfunction "V12A_19") (pintype "power_in"))
      (node (ref "J5") (pin "21") (pinfunction "V12A_21") (pintype "power_in"))
      (node (ref "J5") (pin "23") (pinfunction "V12A_23") (pintype "power_in"))
      (node (ref "J5") (pin "25") (pinfunction "V12A_25") (pintype "power_in"))
      (node (ref "J5") (pin "3") (pinfunction "V12A_3") (pintype "power_in"))
      (node (ref "J5") (pin "5") (pinfunction "V12A_5") (pintype "power_in"))
      (node (ref "J5") (pin "7") (pinfunction "V12A_7") (pintype "power_in"))
      (node (ref "J5") (pin "9") (pinfunction "V12A_9") (pintype "power_in"))
      (node (ref "J6") (pin "1") (pinfunction "V12A_1") (pintype "power_in"))
      (node (ref "J6") (pin "11") (pinfunction "V12A_11") (pintype "power_in"))
      (node (ref "J6") (pin "13") (pinfunction "V12A_13") (pintype "power_in"))
      (node (ref "J6") (pin "15") (pinfunction "V12A_15") (pintype "power_in"))
      (node (ref "J6") (pin "17") (pinfunction "V12A_17") (pintype "power_in"))
      (node (ref "J6") (pin "19") (pinfunction "V12A_19") (pintype "power_in"))
      (node (ref "J6") (pin "21") (pinfunction "V12A_21") (pintype "power_in"))
      (node (ref "J6") (pin "23") (pinfunction "V12A_23") (pintype "power_in"))
      (node (ref "J6") (pin "25") (pinfunction "V12A_25") (pintype "power_in"))
      (node (ref "J6") (pin "3") (pinfunction "V12A_3") (pintype "power_in"))
      (node (ref "J6") (pin "5") (pinfunction "V12A_5") (pintype "power_in"))
      (node (ref "J6") (pin "7") (pinfunction "V12A_7") (pintype "power_in"))
      (node (ref "J6") (pin "9") (pinfunction "V12A_9") (pintype "power_in"))
    )
    (net (code "152") (name "1V2DVFAT1") (class "Default")
      (node (ref "C10") (pin "1") (pinfunction "1_1") (pintype "passive"))
      (node (ref "C12") (pin "1") (pinfunction "1_1") (pintype "passive"))
      (node (ref "C2") (pin "1") (pinfunction "1_1") (pintype "passive"))
      (node (ref "C4") (pin "1") (pinfunction "1_1") (pintype "passive"))
      (node (ref "C6") (pin "1") (pinfunction "1_1") (pintype "passive"))
      (node (ref "C8") (pin "1") (pinfunction "1_1") (pintype "passive"))
      (node (ref "J1") (pin "27") (pinfunction "V12D_27") (pintype "power_in"))
      (node (ref "J1") (pin "29") (pinfunction "V12D_29") (pintype "power_in"))
      (node (ref "J1") (pin "31") (pinfunction "V12D_31") (pintype "power_in"))
      (node (ref "J1") (pin "33") (pinfunction "V12D_33") (pintype "power_in"))
      (node (ref "J1") (pin "35") (pinfunction "V12D_35") (pintype "power_in"))
      (node (ref "J1") (pin "37") (pinfunction "V12D_37") (pintype "power_in"))
      (node (ref "J1") (pin "39") (pinfunction "V12D_39") (pintype "power_in"))
      (node (ref "J1") (pin "41") (pinfunction "V12D_41") (pintype "power_in"))
      (node (ref "J1") (pin "43") (pinfunction "V12D_43") (pintype "power_in"))
      (node (ref "J1") (pin "45") (pinfunction "V12D_45") (pintype "power_in"))
      (node (ref "J1") (pin "47") (pinfunction "V12D_47") (pintype "power_in"))
      (node (ref "J1") (pin "49") (pinfunction "V12D_49") (pintype "power_in"))
      (node (ref "J2") (pin "27") (pinfunction "V12D_27") (pintype "power_in"))
      (node (ref "J2") (pin "29") (pinfunction "V12D_29") (pintype "power_in"))
      (node (ref "J2") (pin "31") (pinfunction "V12D_31") (pintype "power_in"))
      (node (ref "J2") (pin "33") (pinfunction "V12D_33") (pintype "power_in"))
      (node (ref "J2") (pin "35") (pinfunction "V12D_35") (pintype "power_in"))
      (node (ref "J2") (pin "37") (pinfunction "V12D_37") (pintype "power_in"))
      (node (ref "J2") (pin "39") (pinfunction "V12D_39") (pintype "power_in"))
      (node (ref "J2") (pin "41") (pinfunction "V12D_41") (pintype "power_in"))
      (node (ref "J2") (pin "43") (pinfunction "V12D_43") (pintype "power_in"))
      (node (ref "J2") (pin "45") (pinfunction "V12D_45") (pintype "power_in"))
      (node (ref "J2") (pin "47") (pinfunction "V12D_47") (pintype "power_in"))
      (node (ref "J2") (pin "49") (pinfunction "V12D_49") (pintype "power_in"))
      (node (ref "J3") (pin "27") (pinfunction "V12D_27") (pintype "power_in"))
      (node (ref "J3") (pin "29") (pinfunction "V12D_29") (pintype "power_in"))
      (node (ref "J3") (pin "31") (pinfunction "V12D_31") (pintype "power_in"))
      (node (ref "J3") (pin "33") (pinfunction "V12D_33") (pintype "power_in"))
      (node (ref "J3") (pin "35") (pinfunction "V12D_35") (pintype "power_in"))
      (node (ref "J3") (pin "37") (pinfunction "V12D_37") (pintype "power_in"))
      (node (ref "J3") (pin "39") (pinfunction "V12D_39") (pintype "power_in"))
      (node (ref "J3") (pin "41") (pinfunction "V12D_41") (pintype "power_in"))
      (node (ref "J3") (pin "43") (pinfunction "V12D_43") (pintype "power_in"))
      (node (ref "J3") (pin "45") (pinfunction "V12D_45") (pintype "power_in"))
      (node (ref "J3") (pin "47") (pinfunction "V12D_47") (pintype "power_in"))
      (node (ref "J3") (pin "49") (pinfunction "V12D_49") (pintype "power_in"))
      (node (ref "J4") (pin "27") (pinfunction "V12D_27") (pintype "power_in"))
      (node (ref "J4") (pin "29") (pinfunction "V12D_29") (pintype "power_in"))
      (node (ref "J4") (pin "31") (pinfunction "V12D_31") (pintype "power_in"))
      (node (ref "J4") (pin "33") (pinfunction "V12D_33") (pintype "power_in"))
      (node (ref "J4") (pin "35") (pinfunction "V12D_35") (pintype "power_in"))
      (node (ref "J4") (pin "37") (pinfunction "V12D_37") (pintype "power_in"))
      (node (ref "J4") (pin "39") (pinfunction "V12D_39") (pintype "power_in"))
      (node (ref "J4") (pin "41") (pinfunction "V12D_41") (pintype "power_in"))
      (node (ref "J4") (pin "43") (pinfunction "V12D_43") (pintype "power_in"))
      (node (ref "J4") (pin "45") (pinfunction "V12D_45") (pintype "power_in"))
      (node (ref "J4") (pin "47") (pinfunction "V12D_47") (pintype "power_in"))
      (node (ref "J4") (pin "49") (pinfunction "V12D_49") (pintype "power_in"))
      (node (ref "J5") (pin "27") (pinfunction "V12D_27") (pintype "power_in"))
      (node (ref "J5") (pin "29") (pinfunction "V12D_29") (pintype "power_in"))
      (node (ref "J5") (pin "31") (pinfunction "V12D_31") (pintype "power_in"))
      (node (ref "J5") (pin "33") (pinfunction "V12D_33") (pintype "power_in"))
      (node (ref "J5") (pin "35") (pinfunction "V12D_35") (pintype "power_in"))
      (node (ref "J5") (pin "37") (pinfunction "V12D_37") (pintype "power_in"))
      (node (ref "J5") (pin "39") (pinfunction "V12D_39") (pintype "power_in"))
      (node (ref "J5") (pin "41") (pinfunction "V12D_41") (pintype "power_in"))
      (node (ref "J5") (pin "43") (pinfunction "V12D_43") (pintype "power_in"))
      (node (ref "J5") (pin "45") (pinfunction "V12D_45") (pintype "power_in"))
      (node (ref "J5") (pin "47") (pinfunction "V12D_47") (pintype "power_in"))
      (node (ref "J5") (pin "49") (pinfunction "V12D_49") (pintype "power_in"))
      (node (ref "J6") (pin "27") (pinfunction "V12D_27") (pintype "power_in"))
      (node (ref "J6") (pin "29") (pinfunction "V12D_29") (pintype "power_in"))
      (node (ref "J6") (pin "31") (pinfunction "V12D_31") (pintype "power_in"))
      (node (ref "J6") (pin "33") (pinfunction "V12D_33") (pintype "power_in"))
      (node (ref "J6") (pin "35") (pinfunction "V12D_35") (pintype "power_in"))
      (node (ref "J6") (pin "37") (pinfunction "V12D_37") (pintype "power_in"))
      (node (ref "J6") (pin "39") (pinfunction "V12D_39") (pintype "power_in"))
      (node (ref "J6") (pin "41") (pinfunction "V12D_41") (pintype "power_in"))
      (node (ref "J6") (pin "43") (pinfunction "V12D_43") (pintype "power_in"))
      (node (ref "J6") (pin "45") (pinfunction "V12D_45") (pintype "power_in"))
      (node (ref "J6") (pin "47") (pinfunction "V12D_47") (pintype "power_in"))
      (node (ref "J6") (pin "49") (pinfunction "V12D_49") (pintype "power_in"))
    )
    (net (code "153") (name "DGND") (class "Default")
      (node (ref "C10") (pin "2") (pinfunction "2_2") (pintype "passive"))
      (node (ref "C12") (pin "2") (pinfunction "2_2") (pintype "passive"))
      (node (ref "C2") (pin "2") (pinfunction "2_2") (pintype "passive"))
      (node (ref "C4") (pin "2") (pinfunction "2_2") (pintype "passive"))
      (node (ref "C6") (pin "2") (pinfunction "2_2") (pintype "passive"))
      (node (ref "C8") (pin "2") (pinfunction "2_2") (pintype "passive"))
      (node (ref "J1") (pin "75") (pinfunction "DGND_75") (pintype "power_in"))
      (node (ref "J1") (pin "77") (pinfunction "DGND_77") (pintype "power_in"))
      (node (ref "J1") (pin "79") (pinfunction "DGND_79") (pintype "power_in"))
      (node (ref "J1") (pin "81") (pinfunction "DGND_81") (pintype "power_in"))
      (node (ref "J1") (pin "83") (pinfunction "DGND_83") (pintype "power_in"))
      (node (ref "J1") (pin "85") (pinfunction "DGND_85") (pintype "power_in"))
      (node (ref "J1") (pin "87") (pinfunction "DGND_87") (pintype "power_in"))
      (node (ref "J1") (pin "89") (pinfunction "DGND_89") (pintype "power_in"))
      (node (ref "J1") (pin "91") (pinfunction "DGND_91") (pintype "power_in"))
      (node (ref "J1") (pin "93") (pinfunction "DGND_93") (pintype "power_in"))
      (node (ref "J1") (pin "95") (pinfunction "DGND_95") (pintype "power_in"))
      (node (ref "J1") (pin "97") (pinfunction "DGND_97") (pintype "power_in"))
      (node (ref "J1") (pin "99") (pinfunction "DGND_99") (pintype "power_in"))
      (node (ref "J2") (pin "75") (pinfunction "DGND_75") (pintype "power_in"))
      (node (ref "J2") (pin "77") (pinfunction "DGND_77") (pintype "power_in"))
      (node (ref "J2") (pin "79") (pinfunction "DGND_79") (pintype "power_in"))
      (node (ref "J2") (pin "81") (pinfunction "DGND_81") (pintype "power_in"))
      (node (ref "J2") (pin "83") (pinfunction "DGND_83") (pintype "power_in"))
      (node (ref "J2") (pin "85") (pinfunction "DGND_85") (pintype "power_in"))
      (node (ref "J2") (pin "87") (pinfunction "DGND_87") (pintype "power_in"))
      (node (ref "J2") (pin "89") (pinfunction "DGND_89") (pintype "power_in"))
      (node (ref "J2") (pin "91") (pinfunction "DGND_91") (pintype "power_in"))
      (node (ref "J2") (pin "93") (pinfunction "DGND_93") (pintype "power_in"))
      (node (ref "J2") (pin "95") (pinfunction "DGND_95") (pintype "power_in"))
      (node (ref "J2") (pin "97") (pinfunction "DGND_97") (pintype "power_in"))
      (node (ref "J2") (pin "99") (pinfunction "DGND_99") (pintype "power_in"))
      (node (ref "J3") (pin "75") (pinfunction "DGND_75") (pintype "power_in"))
      (node (ref "J3") (pin "77") (pinfunction "DGND_77") (pintype "power_in"))
      (node (ref "J3") (pin "79") (pinfunction "DGND_79") (pintype "power_in"))
      (node (ref "J3") (pin "81") (pinfunction "DGND_81") (pintype "power_in"))
      (node (ref "J3") (pin "83") (pinfunction "DGND_83") (pintype "power_in"))
      (node (ref "J3") (pin "85") (pinfunction "DGND_85") (pintype "power_in"))
      (node (ref "J3") (pin "87") (pinfunction "DGND_87") (pintype "power_in"))
      (node (ref "J3") (pin "89") (pinfunction "DGND_89") (pintype "power_in"))
      (node (ref "J3") (pin "91") (pinfunction "DGND_91") (pintype "power_in"))
      (node (ref "J3") (pin "93") (pinfunction "DGND_93") (pintype "power_in"))
      (node (ref "J3") (pin "95") (pinfunction "DGND_95") (pintype "power_in"))
      (node (ref "J3") (pin "97") (pinfunction "DGND_97") (pintype "power_in"))
      (node (ref "J3") (pin "99") (pinfunction "DGND_99") (pintype "power_in"))
      (node (ref "J4") (pin "75") (pinfunction "DGND_75") (pintype "power_in"))
      (node (ref "J4") (pin "77") (pinfunction "DGND_77") (pintype "power_in"))
      (node (ref "J4") (pin "79") (pinfunction "DGND_79") (pintype "power_in"))
      (node (ref "J4") (pin "81") (pinfunction "DGND_81") (pintype "power_in"))
      (node (ref "J4") (pin "83") (pinfunction "DGND_83") (pintype "power_in"))
      (node (ref "J4") (pin "85") (pinfunction "DGND_85") (pintype "power_in"))
      (node (ref "J4") (pin "87") (pinfunction "DGND_87") (pintype "power_in"))
      (node (ref "J4") (pin "89") (pinfunction "DGND_89") (pintype "power_in"))
      (node (ref "J4") (pin "91") (pinfunction "DGND_91") (pintype "power_in"))
      (node (ref "J4") (pin "93") (pinfunction "DGND_93") (pintype "power_in"))
      (node (ref "J4") (pin "95") (pinfunction "DGND_95") (pintype "power_in"))
      (node (ref "J4") (pin "97") (pinfunction "DGND_97") (pintype "power_in"))
      (node (ref "J4") (pin "99") (pinfunction "DGND_99") (pintype "power_in"))
      (node (ref "J5") (pin "75") (pinfunction "DGND_75") (pintype "power_in"))
      (node (ref "J5") (pin "77") (pinfunction "DGND_77") (pintype "power_in"))
      (node (ref "J5") (pin "79") (pinfunction "DGND_79") (pintype "power_in"))
      (node (ref "J5") (pin "81") (pinfunction "DGND_81") (pintype "power_in"))
      (node (ref "J5") (pin "83") (pinfunction "DGND_83") (pintype "power_in"))
      (node (ref "J5") (pin "85") (pinfunction "DGND_85") (pintype "power_in"))
      (node (ref "J5") (pin "87") (pinfunction "DGND_87") (pintype "power_in"))
      (node (ref "J5") (pin "89") (pinfunction "DGND_89") (pintype "power_in"))
      (node (ref "J5") (pin "91") (pinfunction "DGND_91") (pintype "power_in"))
      (node (ref "J5") (pin "93") (pinfunction "DGND_93") (pintype "power_in"))
      (node (ref "J5") (pin "95") (pinfunction "DGND_95") (pintype "power_in"))
      (node (ref "J5") (pin "97") (pinfunction "DGND_97") (pintype "power_in"))
      (node (ref "J5") (pin "99") (pinfunction "DGND_99") (pintype "power_in"))
      (node (ref "J6") (pin "75") (pinfunction "DGND_75") (pintype "power_in"))
      (node (ref "J6") (pin "77") (pinfunction "DGND_77") (pintype "power_in"))
      (node (ref "J6") (pin "79") (pinfunction "DGND_79") (pintype "power_in"))
      (node (ref "J6") (pin "81") (pinfunction "DGND_81") (pintype "power_in"))
      (node (ref "J6") (pin "83") (pinfunction "DGND_83") (pintype "power_in"))
      (node (ref "J6") (pin "85") (pinfunction "DGND_85") (pintype "power_in"))
      (node (ref "J6") (pin "87") (pinfunction "DGND_87") (pintype "power_in"))
      (node (ref "J6") (pin "89") (pinfunction "DGND_89") (pintype "power_in"))
      (node (ref "J6") (pin "91") (pinfunction "DGND_91") (pintype "power_in"))
      (node (ref "J6") (pin "93") (pinfunction "DGND_93") (pintype "power_in"))
      (node (ref "J6") (pin "95") (pinfunction "DGND_95") (pintype "power_in"))
      (node (ref "J6") (pin "97") (pinfunction "DGND_97") (pintype "power_in"))
      (node (ref "J6") (pin "99") (pinfunction "DGND_99") (pintype "power_in"))
      (node (ref "OH_CONN1") (pin "10") (pinfunction "DGND_10") (pintype "power_in"))
      (node (ref "OH_CONN1") (pin "11") (pinfunction "DGND_11") (pintype "power_in"))
      (node (ref "OH_CONN1") (pin "12") (pinfunction "DGND_12") (pintype "power_in"))
      (node (ref "OH_CONN1") (pin "165") (pinfunction "Bank11_165") (pintype "passive"))
      (node (ref "OH_CONN1") (pin "166") (pinfunction "Bank12_166") (pintype "passive"))
      (node (ref "OH_CONN1") (pin "167") (pinfunction "Bank13_167") (pintype "passive"))
      (node (ref "OH_CONN1") (pin "168") (pinfunction "Bank14_168") (pintype "passive"))
      (node (ref "OH_CONN1") (pin "169") (pinfunction "Bank21_169") (pintype "passive"))
      (node (ref "OH_CONN1") (pin "170") (pinfunction "Bank22_170") (pintype "passive"))
      (node (ref "OH_CONN1") (pin "171") (pinfunction "Bank23_171") (pintype "passive"))
      (node (ref "OH_CONN1") (pin "172") (pinfunction "Bank24_172") (pintype "passive"))
      (node (ref "OH_CONN1") (pin "173") (pinfunction "Bank31_173") (pintype "passive"))
      (node (ref "OH_CONN1") (pin "174") (pinfunction "Bank32_174") (pintype "passive"))
      (node (ref "OH_CONN1") (pin "175") (pinfunction "Bank33_175") (pintype "passive"))
      (node (ref "OH_CONN1") (pin "176") (pinfunction "Bank34_176") (pintype "passive"))
      (node (ref "OH_CONN1") (pin "61") (pinfunction "DGND_61") (pintype "power_in"))
      (node (ref "OH_CONN1") (pin "62") (pinfunction "DGND_62") (pintype "power_in"))
      (node (ref "OH_CONN1") (pin "63") (pinfunction "DGND_63") (pintype "power_in"))
      (node (ref "OH_CONN1") (pin "64") (pinfunction "DGND_64") (pintype "power_in"))
    )
    (net (code "154") (name "Monitor1") (class "Default")
      (node (ref "OH_CONN1") (pin "7") (pinfunction "MONITOR1_7") (pintype "input"))
    )
    (net (code "155") (name "Monitor2") (class "Default")
      (node (ref "OH_CONN1") (pin "8") (pinfunction "MONITOR2_8") (pintype "input"))
    )
    (net (code "156") (name "Monitor3") (class "Default")
      (node (ref "OH_CONN1") (pin "9") (pinfunction "MONITOR3_9") (pintype "input"))
    )
    (net (code "157") (name "PWR1V5") (class "Default")
      (node (ref "OH_CONN1") (pin "161") (pinfunction "Bank01_161") (pintype "passive"))
      (node (ref "OH_CONN1") (pin "162") (pinfunction "Bank02_162") (pintype "passive"))
      (node (ref "OH_CONN1") (pin "163") (pinfunction "Bank03_163") (pintype "passive"))
      (node (ref "OH_CONN1") (pin "164") (pinfunction "Bank04_164") (pintype "passive"))
    )
    (net (code "158") (name "VFATAGND1") (class "Default")
      (node (ref "C1") (pin "2") (pinfunction "2_2") (pintype "passive"))
      (node (ref "C11") (pin "2") (pinfunction "2_2") (pintype "passive"))
      (node (ref "C3") (pin "2") (pinfunction "2_2") (pintype "passive"))
      (node (ref "C5") (pin "2") (pinfunction "2_2") (pintype "passive"))
      (node (ref "C7") (pin "2") (pinfunction "2_2") (pintype "passive"))
      (node (ref "C9") (pin "2") (pinfunction "2_2") (pintype "passive"))
      (node (ref "J1") (pin "51") (pinfunction "AGND_51") (pintype "power_in"))
      (node (ref "J1") (pin "53") (pinfunction "AGND_53") (pintype "power_in"))
      (node (ref "J1") (pin "55") (pinfunction "AGND_55") (pintype "power_in"))
      (node (ref "J1") (pin "57") (pinfunction "AGND_57") (pintype "power_in"))
      (node (ref "J1") (pin "59") (pinfunction "AGND_59") (pintype "power_in"))
      (node (ref "J1") (pin "61") (pinfunction "AGND_61") (pintype "power_in"))
      (node (ref "J1") (pin "63") (pinfunction "AGND_63") (pintype "power_in"))
      (node (ref "J1") (pin "65") (pinfunction "AGND_65") (pintype "power_in"))
      (node (ref "J1") (pin "67") (pinfunction "AGND_67") (pintype "power_in"))
      (node (ref "J1") (pin "69") (pinfunction "AGND_69") (pintype "power_in"))
      (node (ref "J1") (pin "71") (pinfunction "AGND_71") (pintype "power_in"))
      (node (ref "J1") (pin "73") (pinfunction "AGND_73") (pintype "power_in"))
      (node (ref "J2") (pin "51") (pinfunction "AGND_51") (pintype "power_in"))
      (node (ref "J2") (pin "53") (pinfunction "AGND_53") (pintype "power_in"))
      (node (ref "J2") (pin "55") (pinfunction "AGND_55") (pintype "power_in"))
      (node (ref "J2") (pin "57") (pinfunction "AGND_57") (pintype "power_in"))
      (node (ref "J2") (pin "59") (pinfunction "AGND_59") (pintype "power_in"))
      (node (ref "J2") (pin "61") (pinfunction "AGND_61") (pintype "power_in"))
      (node (ref "J2") (pin "63") (pinfunction "AGND_63") (pintype "power_in"))
      (node (ref "J2") (pin "65") (pinfunction "AGND_65") (pintype "power_in"))
      (node (ref "J2") (pin "67") (pinfunction "AGND_67") (pintype "power_in"))
      (node (ref "J2") (pin "69") (pinfunction "AGND_69") (pintype "power_in"))
      (node (ref "J2") (pin "71") (pinfunction "AGND_71") (pintype "power_in"))
      (node (ref "J2") (pin "73") (pinfunction "AGND_73") (pintype "power_in"))
      (node (ref "J3") (pin "51") (pinfunction "AGND_51") (pintype "power_in"))
      (node (ref "J3") (pin "53") (pinfunction "AGND_53") (pintype "power_in"))
      (node (ref "J3") (pin "55") (pinfunction "AGND_55") (pintype "power_in"))
      (node (ref "J3") (pin "57") (pinfunction "AGND_57") (pintype "power_in"))
      (node (ref "J3") (pin "59") (pinfunction "AGND_59") (pintype "power_in"))
      (node (ref "J3") (pin "61") (pinfunction "AGND_61") (pintype "power_in"))
      (node (ref "J3") (pin "63") (pinfunction "AGND_63") (pintype "power_in"))
      (node (ref "J3") (pin "65") (pinfunction "AGND_65") (pintype "power_in"))
      (node (ref "J3") (pin "67") (pinfunction "AGND_67") (pintype "power_in"))
      (node (ref "J3") (pin "69") (pinfunction "AGND_69") (pintype "power_in"))
      (node (ref "J3") (pin "71") (pinfunction "AGND_71") (pintype "power_in"))
      (node (ref "J3") (pin "73") (pinfunction "AGND_73") (pintype "power_in"))
      (node (ref "J4") (pin "51") (pinfunction "AGND_51") (pintype "power_in"))
      (node (ref "J4") (pin "53") (pinfunction "AGND_53") (pintype "power_in"))
      (node (ref "J4") (pin "55") (pinfunction "AGND_55") (pintype "power_in"))
      (node (ref "J4") (pin "57") (pinfunction "AGND_57") (pintype "power_in"))
      (node (ref "J4") (pin "59") (pinfunction "AGND_59") (pintype "power_in"))
      (node (ref "J4") (pin "61") (pinfunction "AGND_61") (pintype "power_in"))
      (node (ref "J4") (pin "63") (pinfunction "AGND_63") (pintype "power_in"))
      (node (ref "J4") (pin "65") (pinfunction "AGND_65") (pintype "power_in"))
      (node (ref "J4") (pin "67") (pinfunction "AGND_67") (pintype "power_in"))
      (node (ref "J4") (pin "69") (pinfunction "AGND_69") (pintype "power_in"))
      (node (ref "J4") (pin "71") (pinfunction "AGND_71") (pintype "power_in"))
      (node (ref "J4") (pin "73") (pinfunction "AGND_73") (pintype "power_in"))
      (node (ref "J5") (pin "51") (pinfunction "AGND_51") (pintype "power_in"))
      (node (ref "J5") (pin "53") (pinfunction "AGND_53") (pintype "power_in"))
      (node (ref "J5") (pin "55") (pinfunction "AGND_55") (pintype "power_in"))
      (node (ref "J5") (pin "57") (pinfunction "AGND_57") (pintype "power_in"))
      (node (ref "J5") (pin "59") (pinfunction "AGND_59") (pintype "power_in"))
      (node (ref "J5") (pin "61") (pinfunction "AGND_61") (pintype "power_in"))
      (node (ref "J5") (pin "63") (pinfunction "AGND_63") (pintype "power_in"))
      (node (ref "J5") (pin "65") (pinfunction "AGND_65") (pintype "power_in"))
      (node (ref "J5") (pin "67") (pinfunction "AGND_67") (pintype "power_in"))
      (node (ref "J5") (pin "69") (pinfunction "AGND_69") (pintype "power_in"))
      (node (ref "J5") (pin "71") (pinfunction "AGND_71") (pintype "power_in"))
      (node (ref "J5") (pin "73") (pinfunction "AGND_73") (pintype "power_in"))
      (node (ref "J6") (pin "51") (pinfunction "AGND_51") (pintype "power_in"))
      (node (ref "J6") (pin "53") (pinfunction "AGND_53") (pintype "power_in"))
      (node (ref "J6") (pin "55") (pinfunction "AGND_55") (pintype "power_in"))
      (node (ref "J6") (pin "57") (pinfunction "AGND_57") (pintype "power_in"))
      (node (ref "J6") (pin "59") (pinfunction "AGND_59") (pintype "power_in"))
      (node (ref "J6") (pin "61") (pinfunction "AGND_61") (pintype "power_in"))
      (node (ref "J6") (pin "63") (pinfunction "AGND_63") (pintype "power_in"))
      (node (ref "J6") (pin "65") (pinfunction "AGND_65") (pintype "power_in"))
      (node (ref "J6") (pin "67") (pinfunction "AGND_67") (pintype "power_in"))
      (node (ref "J6") (pin "69") (pinfunction "AGND_69") (pintype "power_in"))
      (node (ref "J6") (pin "71") (pinfunction "AGND_71") (pintype "power_in"))
      (node (ref "J6") (pin "73") (pinfunction "AGND_73") (pintype "power_in"))
    )
    (net (code "159") (name "unconnected-(J1-Pad2)") (class "Default")
      (node (ref "J1") (pin "2") (pinfunction "2_2") (pintype "passive"))
    )
    (net (code "160") (name "unconnected-(J1-Pad4)") (class "Default")
      (node (ref "J1") (pin "4") (pinfunction "4_4") (pintype "passive"))
    )
    (net (code "161") (name "unconnected-(J1-Pad6)") (class "Default")
      (node (ref "J1") (pin "6") (pinfunction "6_6") (pintype "passive"))
    )
    (net (code "162") (name "unconnected-(J1-Pad8)") (class "Default")
      (node (ref "J1") (pin "8") (pinfunction "8_8") (pintype "passive"))
    )
    (net (code "163") (name "unconnected-(J1-Pad10)") (class "Default")
      (node (ref "J1") (pin "10") (pinfunction "10_10") (pintype "passive"))
    )
    (net (code "164") (name "unconnected-(J1-Pad12)") (class "Default")
      (node (ref "J1") (pin "12") (pinfunction "12_12") (pintype "passive"))
    )
    (net (code "165") (name "unconnected-(J1-Pad14)") (class "Default")
      (node (ref "J1") (pin "14") (pinfunction "14_14") (pintype "passive"))
    )
    (net (code "166") (name "unconnected-(J1-Pad16)") (class "Default")
      (node (ref "J1") (pin "16") (pinfunction "16_16") (pintype "passive"))
    )
    (net (code "167") (name "unconnected-(J1-Pad18)") (class "Default")
      (node (ref "J1") (pin "18") (pinfunction "18_18") (pintype "passive"))
    )
    (net (code "168") (name "unconnected-(J1-Pad20)") (class "Default")
      (node (ref "J1") (pin "20") (pinfunction "20_20") (pintype "passive"))
    )
    (net (code "169") (name "unconnected-(J1-Pad22)") (class "Default")
      (node (ref "J1") (pin "22") (pinfunction "22_22") (pintype "passive"))
    )
    (net (code "170") (name "unconnected-(J1-Pad24)") (class "Default")
      (node (ref "J1") (pin "24") (pinfunction "24_24") (pintype "passive"))
    )
    (net (code "171") (name "unconnected-(J1-Pad26)") (class "Default")
      (node (ref "J1") (pin "26") (pinfunction "26_26") (pintype "passive"))
    )
    (net (code "172") (name "unconnected-(J1-Pad28)") (class "Default")
      (node (ref "J1") (pin "28") (pinfunction "28_28") (pintype "passive"))
    )
    (net (code "173") (name "unconnected-(J1-Pad30)") (class "Default")
      (node (ref "J1") (pin "30") (pinfunction "30_30") (pintype "passive"))
    )
    (net (code "174") (name "unconnected-(J1-Pad32)") (class "Default")
      (node (ref "J1") (pin "32") (pinfunction "32_32") (pintype "passive"))
    )
    (net (code "175") (name "unconnected-(J1-Pad34)") (class "Default")
      (node (ref "J1") (pin "34") (pinfunction "34_34") (pintype "passive"))
    )
    (net (code "176") (name "unconnected-(J1-Pad36)") (class "Default")
      (node (ref "J1") (pin "36") (pinfunction "36_36") (pintype "passive"))
    )
    (net (code "177") (name "unconnected-(J1-Pad38)") (class "Default")
      (node (ref "J1") (pin "38") (pinfunction "38_38") (pintype "passive"))
    )
    (net (code "178") (name "unconnected-(J1-Pad40)") (class "Default")
      (node (ref "J1") (pin "40") (pinfunction "40_40") (pintype "passive"))
    )
    (net (code "179") (name "unconnected-(J1-Pad42)") (class "Default")
      (node (ref "J1") (pin "42") (pinfunction "42_42") (pintype "passive"))
    )
    (net (code "180") (name "unconnected-(J1-Pad44)") (class "Default")
      (node (ref "J1") (pin "44") (pinfunction "44_44") (pintype "passive"))
    )
    (net (code "181") (name "unconnected-(J1-Pad46)") (class "Default")
      (node (ref "J1") (pin "46") (pinfunction "46_46") (pintype "passive"))
    )
    (net (code "182") (name "unconnected-(J1-Pad48)") (class "Default")
      (node (ref "J1") (pin "48") (pinfunction "48_48") (pintype "passive"))
    )
    (net (code "183") (name "unconnected-(J1-Pad50)") (class "Default")
      (node (ref "J1") (pin "50") (pinfunction "50_50") (pintype "passive"))
    )
    (net (code "184") (name "unconnected-(J2-Pad2)") (class "Default")
      (node (ref "J2") (pin "2") (pinfunction "2_2") (pintype "passive"))
    )
    (net (code "185") (name "unconnected-(J2-Pad4)") (class "Default")
      (node (ref "J2") (pin "4") (pinfunction "4_4") (pintype "passive"))
    )
    (net (code "186") (name "unconnected-(J2-Pad6)") (class "Default")
      (node (ref "J2") (pin "6") (pinfunction "6_6") (pintype "passive"))
    )
    (net (code "187") (name "unconnected-(J2-Pad8)") (class "Default")
      (node (ref "J2") (pin "8") (pinfunction "8_8") (pintype "passive"))
    )
    (net (code "188") (name "unconnected-(J2-Pad10)") (class "Default")
      (node (ref "J2") (pin "10") (pinfunction "10_10") (pintype "passive"))
    )
    (net (code "189") (name "unconnected-(J2-Pad12)") (class "Default")
      (node (ref "J2") (pin "12") (pinfunction "12_12") (pintype "passive"))
    )
    (net (code "190") (name "unconnected-(J2-Pad14)") (class "Default")
      (node (ref "J2") (pin "14") (pinfunction "14_14") (pintype "passive"))
    )
    (net (code "191") (name "unconnected-(J2-Pad16)") (class "Default")
      (node (ref "J2") (pin "16") (pinfunction "16_16") (pintype "passive"))
    )
    (net (code "192") (name "unconnected-(J2-Pad18)") (class "Default")
      (node (ref "J2") (pin "18") (pinfunction "18_18") (pintype "passive"))
    )
    (net (code "193") (name "unconnected-(J2-Pad20)") (class "Default")
      (node (ref "J2") (pin "20") (pinfunction "20_20") (pintype "passive"))
    )
    (net (code "194") (name "unconnected-(J2-Pad22)") (class "Default")
      (node (ref "J2") (pin "22") (pinfunction "22_22") (pintype "passive"))
    )
    (net (code "195") (name "unconnected-(J2-Pad24)") (class "Default")
      (node (ref "J2") (pin "24") (pinfunction "24_24") (pintype "passive"))
    )
    (net (code "196") (name "unconnected-(J2-Pad26)") (class "Default")
      (node (ref "J2") (pin "26") (pinfunction "26_26") (pintype "passive"))
    )
    (net (code "197") (name "unconnected-(J2-Pad28)") (class "Default")
      (node (ref "J2") (pin "28") (pinfunction "28_28") (pintype "passive"))
    )
    (net (code "198") (name "unconnected-(J2-Pad30)") (class "Default")
      (node (ref "J2") (pin "30") (pinfunction "30_30") (pintype "passive"))
    )
    (net (code "199") (name "unconnected-(J2-Pad32)") (class "Default")
      (node (ref "J2") (pin "32") (pinfunction "32_32") (pintype "passive"))
    )
    (net (code "200") (name "unconnected-(J2-Pad34)") (class "Default")
      (node (ref "J2") (pin "34") (pinfunction "34_34") (pintype "passive"))
    )
    (net (code "201") (name "unconnected-(J2-Pad36)") (class "Default")
      (node (ref "J2") (pin "36") (pinfunction "36_36") (pintype "passive"))
    )
    (net (code "202") (name "unconnected-(J2-Pad38)") (class "Default")
      (node (ref "J2") (pin "38") (pinfunction "38_38") (pintype "passive"))
    )
    (net (code "203") (name "unconnected-(J2-Pad40)") (class "Default")
      (node (ref "J2") (pin "40") (pinfunction "40_40") (pintype "passive"))
    )
    (net (code "204") (name "unconnected-(J2-Pad42)") (class "Default")
      (node (ref "J2") (pin "42") (pinfunction "42_42") (pintype "passive"))
    )
    (net (code "205") (name "unconnected-(J2-Pad44)") (class "Default")
      (node (ref "J2") (pin "44") (pinfunction "44_44") (pintype "passive"))
    )
    (net (code "206") (name "unconnected-(J2-Pad46)") (class "Default")
      (node (ref "J2") (pin "46") (pinfunction "46_46") (pintype "passive"))
    )
    (net (code "207") (name "unconnected-(J2-Pad48)") (class "Default")
      (node (ref "J2") (pin "48") (pinfunction "48_48") (pintype "passive"))
    )
    (net (code "208") (name "unconnected-(J2-Pad50)") (class "Default")
      (node (ref "J2") (pin "50") (pinfunction "50_50") (pintype "passive"))
    )
    (net (code "209") (name "unconnected-(J3-Pad2)") (class "Default")
      (node (ref "J3") (pin "2") (pinfunction "2_2") (pintype "passive"))
    )
    (net (code "210") (name "unconnected-(J3-Pad4)") (class "Default")
      (node (ref "J3") (pin "4") (pinfunction "4_4") (pintype "passive"))
    )
    (net (code "211") (name "unconnected-(J3-Pad6)") (class "Default")
      (node (ref "J3") (pin "6") (pinfunction "6_6") (pintype "passive"))
    )
    (net (code "212") (name "unconnected-(J3-Pad8)") (class "Default")
      (node (ref "J3") (pin "8") (pinfunction "8_8") (pintype "passive"))
    )
    (net (code "213") (name "unconnected-(J3-Pad10)") (class "Default")
      (node (ref "J3") (pin "10") (pinfunction "10_10") (pintype "passive"))
    )
    (net (code "214") (name "unconnected-(J3-Pad12)") (class "Default")
      (node (ref "J3") (pin "12") (pinfunction "12_12") (pintype "passive"))
    )
    (net (code "215") (name "unconnected-(J3-Pad14)") (class "Default")
      (node (ref "J3") (pin "14") (pinfunction "14_14") (pintype "passive"))
    )
    (net (code "216") (name "unconnected-(J3-Pad16)") (class "Default")
      (node (ref "J3") (pin "16") (pinfunction "16_16") (pintype "passive"))
    )
    (net (code "217") (name "unconnected-(J3-Pad18)") (class "Default")
      (node (ref "J3") (pin "18") (pinfunction "18_18") (pintype "passive"))
    )
    (net (code "218") (name "unconnected-(J3-Pad20)") (class "Default")
      (node (ref "J3") (pin "20") (pinfunction "20_20") (pintype "passive"))
    )
    (net (code "219") (name "unconnected-(J3-Pad22)") (class "Default")
      (node (ref "J3") (pin "22") (pinfunction "22_22") (pintype "passive"))
    )
    (net (code "220") (name "unconnected-(J3-Pad24)") (class "Default")
      (node (ref "J3") (pin "24") (pinfunction "24_24") (pintype "passive"))
    )
    (net (code "221") (name "unconnected-(J3-Pad26)") (class "Default")
      (node (ref "J3") (pin "26") (pinfunction "26_26") (pintype "passive"))
    )
    (net (code "222") (name "unconnected-(J3-Pad28)") (class "Default")
      (node (ref "J3") (pin "28") (pinfunction "28_28") (pintype "passive"))
    )
    (net (code "223") (name "unconnected-(J3-Pad30)") (class "Default")
      (node (ref "J3") (pin "30") (pinfunction "30_30") (pintype "passive"))
    )
    (net (code "224") (name "unconnected-(J3-Pad32)") (class "Default")
      (node (ref "J3") (pin "32") (pinfunction "32_32") (pintype "passive"))
    )
    (net (code "225") (name "unconnected-(J3-Pad34)") (class "Default")
      (node (ref "J3") (pin "34") (pinfunction "34_34") (pintype "passive"))
    )
    (net (code "226") (name "unconnected-(J3-Pad36)") (class "Default")
      (node (ref "J3") (pin "36") (pinfunction "36_36") (pintype "passive"))
    )
    (net (code "227") (name "unconnected-(J3-Pad38)") (class "Default")
      (node (ref "J3") (pin "38") (pinfunction "38_38") (pintype "passive"))
    )
    (net (code "228") (name "unconnected-(J3-Pad40)") (class "Default")
      (node (ref "J3") (pin "40") (pinfunction "40_40") (pintype "passive"))
    )
    (net (code "229") (name "unconnected-(J3-Pad42)") (class "Default")
      (node (ref "J3") (pin "42") (pinfunction "42_42") (pintype "passive"))
    )
    (net (code "230") (name "unconnected-(J3-Pad44)") (class "Default")
      (node (ref "J3") (pin "44") (pinfunction "44_44") (pintype "passive"))
    )
    (net (code "231") (name "unconnected-(J3-Pad46)") (class "Default")
      (node (ref "J3") (pin "46") (pinfunction "46_46") (pintype "passive"))
    )
    (net (code "232") (name "unconnected-(J3-Pad48)") (class "Default")
      (node (ref "J3") (pin "48") (pinfunction "48_48") (pintype "passive"))
    )
    (net (code "233") (name "unconnected-(J3-Pad50)") (class "Default")
      (node (ref "J3") (pin "50") (pinfunction "50_50") (pintype "passive"))
    )
    (net (code "234") (name "unconnected-(J4-Pad2)") (class "Default")
      (node (ref "J4") (pin "2") (pinfunction "2_2") (pintype "passive"))
    )
    (net (code "235") (name "unconnected-(J4-Pad4)") (class "Default")
      (node (ref "J4") (pin "4") (pinfunction "4_4") (pintype "passive"))
    )
    (net (code "236") (name "unconnected-(J4-Pad6)") (class "Default")
      (node (ref "J4") (pin "6") (pinfunction "6_6") (pintype "passive"))
    )
    (net (code "237") (name "unconnected-(J4-Pad8)") (class "Default")
      (node (ref "J4") (pin "8") (pinfunction "8_8") (pintype "passive"))
    )
    (net (code "238") (name "unconnected-(J4-Pad10)") (class "Default")
      (node (ref "J4") (pin "10") (pinfunction "10_10") (pintype "passive"))
    )
    (net (code "239") (name "unconnected-(J4-Pad12)") (class "Default")
      (node (ref "J4") (pin "12") (pinfunction "12_12") (pintype "passive"))
    )
    (net (code "240") (name "unconnected-(J4-Pad14)") (class "Default")
      (node (ref "J4") (pin "14") (pinfunction "14_14") (pintype "passive"))
    )
    (net (code "241") (name "unconnected-(J4-Pad16)") (class "Default")
      (node (ref "J4") (pin "16") (pinfunction "16_16") (pintype "passive"))
    )
    (net (code "242") (name "unconnected-(J4-Pad18)") (class "Default")
      (node (ref "J4") (pin "18") (pinfunction "18_18") (pintype "passive"))
    )
    (net (code "243") (name "unconnected-(J4-Pad20)") (class "Default")
      (node (ref "J4") (pin "20") (pinfunction "20_20") (pintype "passive"))
    )
    (net (code "244") (name "unconnected-(J4-Pad22)") (class "Default")
      (node (ref "J4") (pin "22") (pinfunction "22_22") (pintype "passive"))
    )
    (net (code "245") (name "unconnected-(J4-Pad24)") (class "Default")
      (node (ref "J4") (pin "24") (pinfunction "24_24") (pintype "passive"))
    )
    (net (code "246") (name "unconnected-(J4-Pad26)") (class "Default")
      (node (ref "J4") (pin "26") (pinfunction "26_26") (pintype "passive"))
    )
    (net (code "247") (name "unconnected-(J4-Pad28)") (class "Default")
      (node (ref "J4") (pin "28") (pinfunction "28_28") (pintype "passive"))
    )
    (net (code "248") (name "unconnected-(J4-Pad30)") (class "Default")
      (node (ref "J4") (pin "30") (pinfunction "30_30") (pintype "passive"))
    )
    (net (code "249") (name "unconnected-(J4-Pad32)") (class "Default")
      (node (ref "J4") (pin "32") (pinfunction "32_32") (pintype "passive"))
    )
    (net (code "250") (name "unconnected-(J4-Pad34)") (class "Default")
      (node (ref "J4") (pin "34") (pinfunction "34_34") (pintype "passive"))
    )
    (net (code "251") (name "unconnected-(J4-Pad36)") (class "Default")
      (node (ref "J4") (pin "36") (pinfunction "36_36") (pintype "passive"))
    )
    (net (code "252") (name "unconnected-(J4-Pad38)") (class "Default")
      (node (ref "J4") (pin "38") (pinfunction "38_38") (pintype "passive"))
    )
    (net (code "253") (name "unconnected-(J4-Pad40)") (class "Default")
      (node (ref "J4") (pin "40") (pinfunction "40_40") (pintype "passive"))
    )
    (net (code "254") (name "unconnected-(J4-Pad42)") (class "Default")
      (node (ref "J4") (pin "42") (pinfunction "42_42") (pintype "passive"))
    )
    (net (code "255") (name "unconnected-(J4-Pad44)") (class "Default")
      (node (ref "J4") (pin "44") (pinfunction "44_44") (pintype "passive"))
    )
    (net (code "256") (name "unconnected-(J4-Pad46)") (class "Default")
      (node (ref "J4") (pin "46") (pinfunction "46_46") (pintype "passive"))
    )
    (net (code "257") (name "unconnected-(J4-Pad48)") (class "Default")
      (node (ref "J4") (pin "48") (pinfunction "48_48") (pintype "passive"))
    )
    (net (code "258") (name "unconnected-(J4-Pad50)") (class "Default")
      (node (ref "J4") (pin "50") (pinfunction "50_50") (pintype "passive"))
    )
    (net (code "259") (name "unconnected-(J5-Pad2)") (class "Default")
      (node (ref "J5") (pin "2") (pinfunction "2_2") (pintype "passive"))
    )
    (net (code "260") (name "unconnected-(J5-Pad4)") (class "Default")
      (node (ref "J5") (pin "4") (pinfunction "4_4") (pintype "passive"))
    )
    (net (code "261") (name "unconnected-(J5-Pad6)") (class "Default")
      (node (ref "J5") (pin "6") (pinfunction "6_6") (pintype "passive"))
    )
    (net (code "262") (name "unconnected-(J5-Pad8)") (class "Default")
      (node (ref "J5") (pin "8") (pinfunction "8_8") (pintype "passive"))
    )
    (net (code "263") (name "unconnected-(J5-Pad10)") (class "Default")
      (node (ref "J5") (pin "10") (pinfunction "10_10") (pintype "passive"))
    )
    (net (code "264") (name "unconnected-(J5-Pad12)") (class "Default")
      (node (ref "J5") (pin "12") (pinfunction "12_12") (pintype "passive"))
    )
    (net (code "265") (name "unconnected-(J5-Pad14)") (class "Default")
      (node (ref "J5") (pin "14") (pinfunction "14_14") (pintype "passive"))
    )
    (net (code "266") (name "unconnected-(J5-Pad16)") (class "Default")
      (node (ref "J5") (pin "16") (pinfunction "16_16") (pintype "passive"))
    )
    (net (code "267") (name "unconnected-(J5-Pad18)") (class "Default")
      (node (ref "J5") (pin "18") (pinfunction "18_18") (pintype "passive"))
    )
    (net (code "268") (name "unconnected-(J5-Pad20)") (class "Default")
      (node (ref "J5") (pin "20") (pinfunction "20_20") (pintype "passive"))
    )
    (net (code "269") (name "unconnected-(J5-Pad22)") (class "Default")
      (node (ref "J5") (pin "22") (pinfunction "22_22") (pintype "passive"))
    )
    (net (code "270") (name "unconnected-(J5-Pad24)") (class "Default")
      (node (ref "J5") (pin "24") (pinfunction "24_24") (pintype "passive"))
    )
    (net (code "271") (name "unconnected-(J5-Pad26)") (class "Default")
      (node (ref "J5") (pin "26") (pinfunction "26_26") (pintype "passive"))
    )
    (net (code "272") (name "unconnected-(J5-Pad28)") (class "Default")
      (node (ref "J5") (pin "28") (pinfunction "28_28") (pintype "passive"))
    )
    (net (code "273") (name "unconnected-(J5-Pad30)") (class "Default")
      (node (ref "J5") (pin "30") (pinfunction "30_30") (pintype "passive"))
    )
    (net (code "274") (name "unconnected-(J5-Pad32)") (class "Default")
      (node (ref "J5") (pin "32") (pinfunction "32_32") (pintype "passive"))
    )
    (net (code "275") (name "unconnected-(J5-Pad34)") (class "Default")
      (node (ref "J5") (pin "34") (pinfunction "34_34") (pintype "passive"))
    )
    (net (code "276") (name "unconnected-(J5-Pad36)") (class "Default")
      (node (ref "J5") (pin "36") (pinfunction "36_36") (pintype "passive"))
    )
    (net (code "277") (name "unconnected-(J5-Pad38)") (class "Default")
      (node (ref "J5") (pin "38") (pinfunction "38_38") (pintype "passive"))
    )
    (net (code "278") (name "unconnected-(J5-Pad40)") (class "Default")
      (node (ref "J5") (pin "40") (pinfunction "40_40") (pintype "passive"))
    )
    (net (code "279") (name "unconnected-(J5-Pad42)") (class "Default")
      (node (ref "J5") (pin "42") (pinfunction "42_42") (pintype "passive"))
    )
    (net (code "280") (name "unconnected-(J5-Pad44)") (class "Default")
      (node (ref "J5") (pin "44") (pinfunction "44_44") (pintype "passive"))
    )
    (net (code "281") (name "unconnected-(J5-Pad46)") (class "Default")
      (node (ref "J5") (pin "46") (pinfunction "46_46") (pintype "passive"))
    )
    (net (code "282") (name "unconnected-(J5-Pad48)") (class "Default")
      (node (ref "J5") (pin "48") (pinfunction "48_48") (pintype "passive"))
    )
    (net (code "283") (name "unconnected-(J5-Pad50)") (class "Default")
      (node (ref "J5") (pin "50") (pinfunction "50_50") (pintype "passive"))
    )
    (net (code "284") (name "unconnected-(J6-Pad2)") (class "Default")
      (node (ref "J6") (pin "2") (pinfunction "2_2") (pintype "passive"))
    )
    (net (code "285") (name "unconnected-(J6-Pad4)") (class "Default")
      (node (ref "J6") (pin "4") (pinfunction "4_4") (pintype "passive"))
    )
    (net (code "286") (name "unconnected-(J6-Pad6)") (class "Default")
      (node (ref "J6") (pin "6") (pinfunction "6_6") (pintype "passive"))
    )
    (net (code "287") (name "unconnected-(J6-Pad8)") (class "Default")
      (node (ref "J6") (pin "8") (pinfunction "8_8") (pintype "passive"))
    )
    (net (code "288") (name "unconnected-(J6-Pad10)") (class "Default")
      (node (ref "J6") (pin "10") (pinfunction "10_10") (pintype "passive"))
    )
    (net (code "289") (name "unconnected-(J6-Pad12)") (class "Default")
      (node (ref "J6") (pin "12") (pinfunction "12_12") (pintype "passive"))
    )
    (net (code "290") (name "unconnected-(J6-Pad14)") (class "Default")
      (node (ref "J6") (pin "14") (pinfunction "14_14") (pintype "passive"))
    )
    (net (code "291") (name "unconnected-(J6-Pad16)") (class "Default")
      (node (ref "J6") (pin "16") (pinfunction "16_16") (pintype "passive"))
    )
    (net (code "292") (name "unconnected-(J6-Pad18)") (class "Default")
      (node (ref "J6") (pin "18") (pinfunction "18_18") (pintype "passive"))
    )
    (net (code "293") (name "unconnected-(J6-Pad20)") (class "Default")
      (node (ref "J6") (pin "20") (pinfunction "20_20") (pintype "passive"))
    )
    (net (code "294") (name "unconnected-(J6-Pad22)") (class "Default")
      (node (ref "J6") (pin "22") (pinfunction "22_22") (pintype "passive"))
    )
    (net (code "295") (name "unconnected-(J6-Pad24)") (class "Default")
      (node (ref "J6") (pin "24") (pinfunction "24_24") (pintype "passive"))
    )
    (net (code "296") (name "unconnected-(J6-Pad26)") (class "Default")
      (node (ref "J6") (pin "26") (pinfunction "26_26") (pintype "passive"))
    )
    (net (code "297") (name "unconnected-(J6-Pad28)") (class "Default")
      (node (ref "J6") (pin "28") (pinfunction "28_28") (pintype "passive"))
    )
    (net (code "298") (name "unconnected-(J6-Pad30)") (class "Default")
      (node (ref "J6") (pin "30") (pinfunction "30_30") (pintype "passive"))
    )
    (net (code "299") (name "unconnected-(J6-Pad32)") (class "Default")
      (node (ref "J6") (pin "32") (pinfunction "32_32") (pintype "passive"))
    )
    (net (code "300") (name "unconnected-(J6-Pad34)") (class "Default")
      (node (ref "J6") (pin "34") (pinfunction "34_34") (pintype "passive"))
    )
    (net (code "301") (name "unconnected-(J6-Pad36)") (class "Default")
      (node (ref "J6") (pin "36") (pinfunction "36_36") (pintype "passive"))
    )
    (net (code "302") (name "unconnected-(J6-Pad38)") (class "Default")
      (node (ref "J6") (pin "38") (pinfunction "38_38") (pintype "passive"))
    )
    (net (code "303") (name "unconnected-(J6-Pad40)") (class "Default")
      (node (ref "J6") (pin "40") (pinfunction "40_40") (pintype "passive"))
    )
    (net (code "304") (name "unconnected-(J6-Pad42)") (class "Default")
      (node (ref "J6") (pin "42") (pinfunction "42_42") (pintype "passive"))
    )
    (net (code "305") (name "unconnected-(J6-Pad44)") (class "Default")
      (node (ref "J6") (pin "44") (pinfunction "44_44") (pintype "passive"))
    )
    (net (code "306") (name "unconnected-(J6-Pad46)") (class "Default")
      (node (ref "J6") (pin "46") (pinfunction "46_46") (pintype "passive"))
    )
    (net (code "307") (name "unconnected-(J6-Pad48)") (class "Default")
      (node (ref "J6") (pin "48") (pinfunction "48_48") (pintype "passive"))
    )
    (net (code "308") (name "unconnected-(J6-Pad50)") (class "Default")
      (node (ref "J6") (pin "50") (pinfunction "50_50") (pintype "passive"))
    )
  )
)
